# NB-IoT_1_0_0_final.net
KiCad netlist of a schematic drawn in Altium Designer
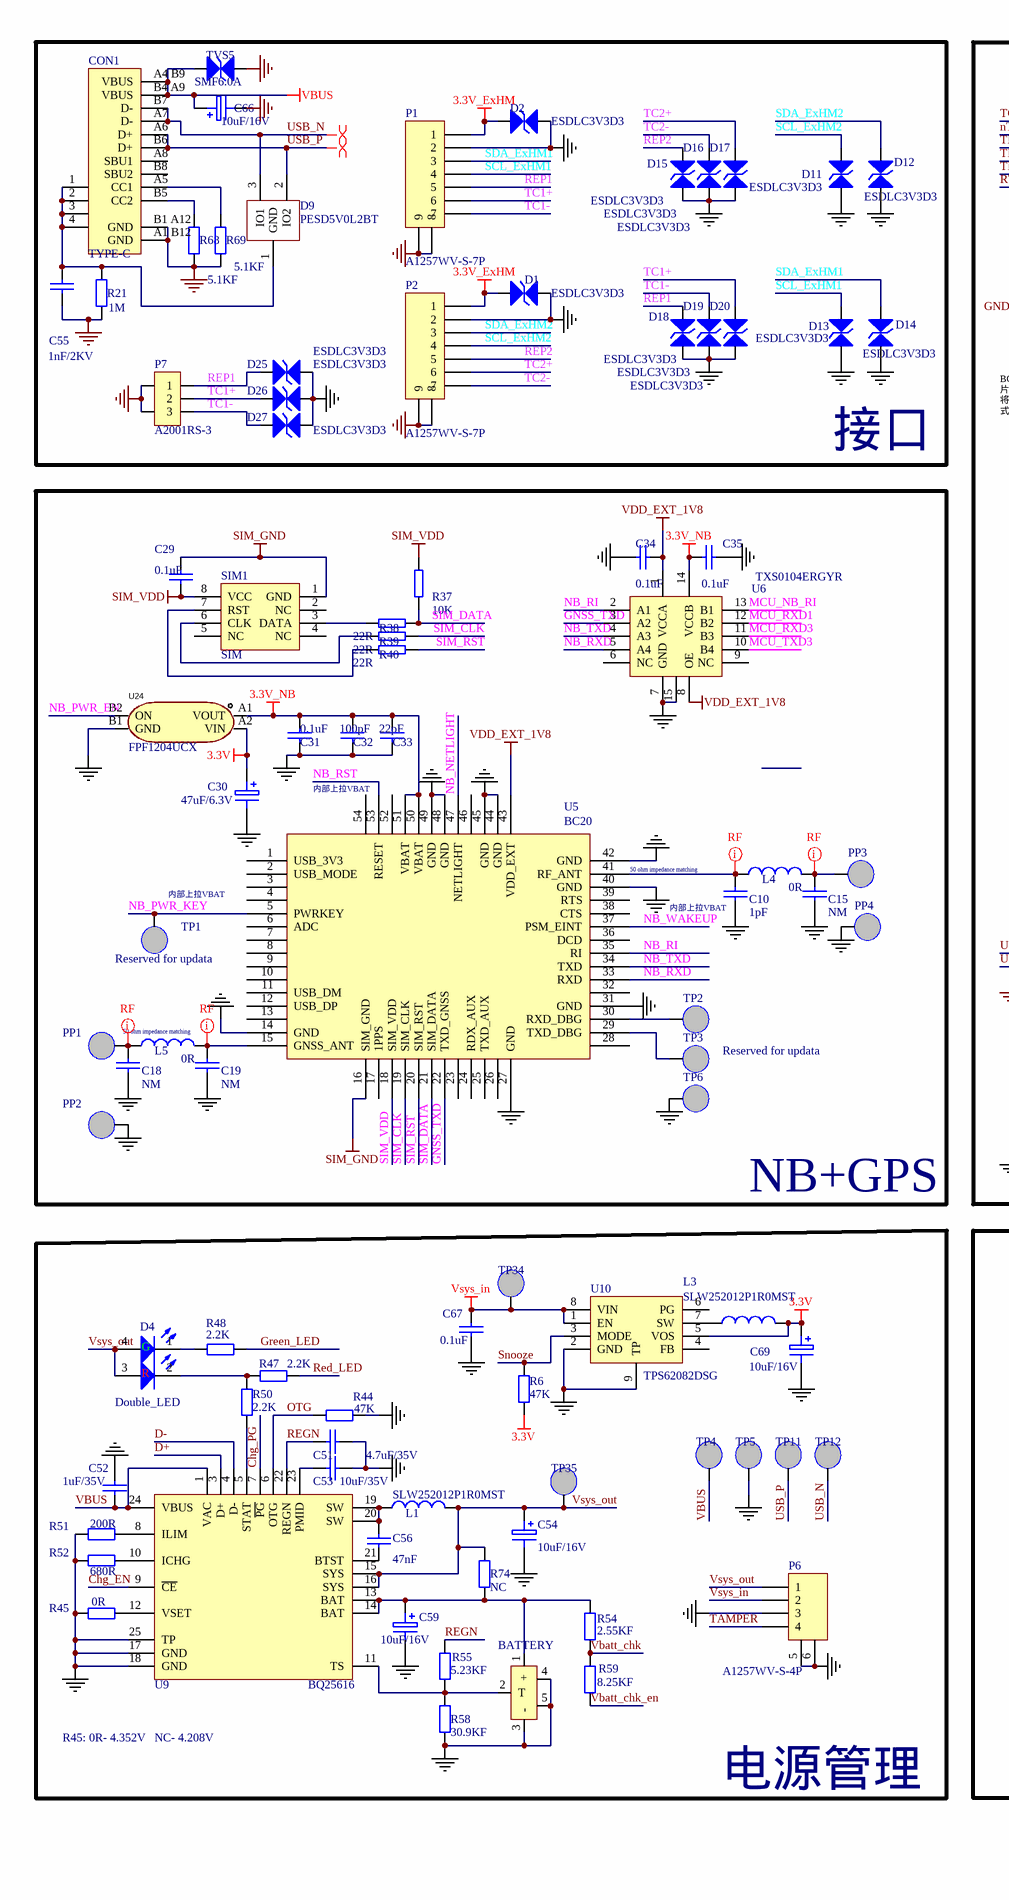
[diagram p0: NB-IoT_1.0.0_final.SchDoc, left]
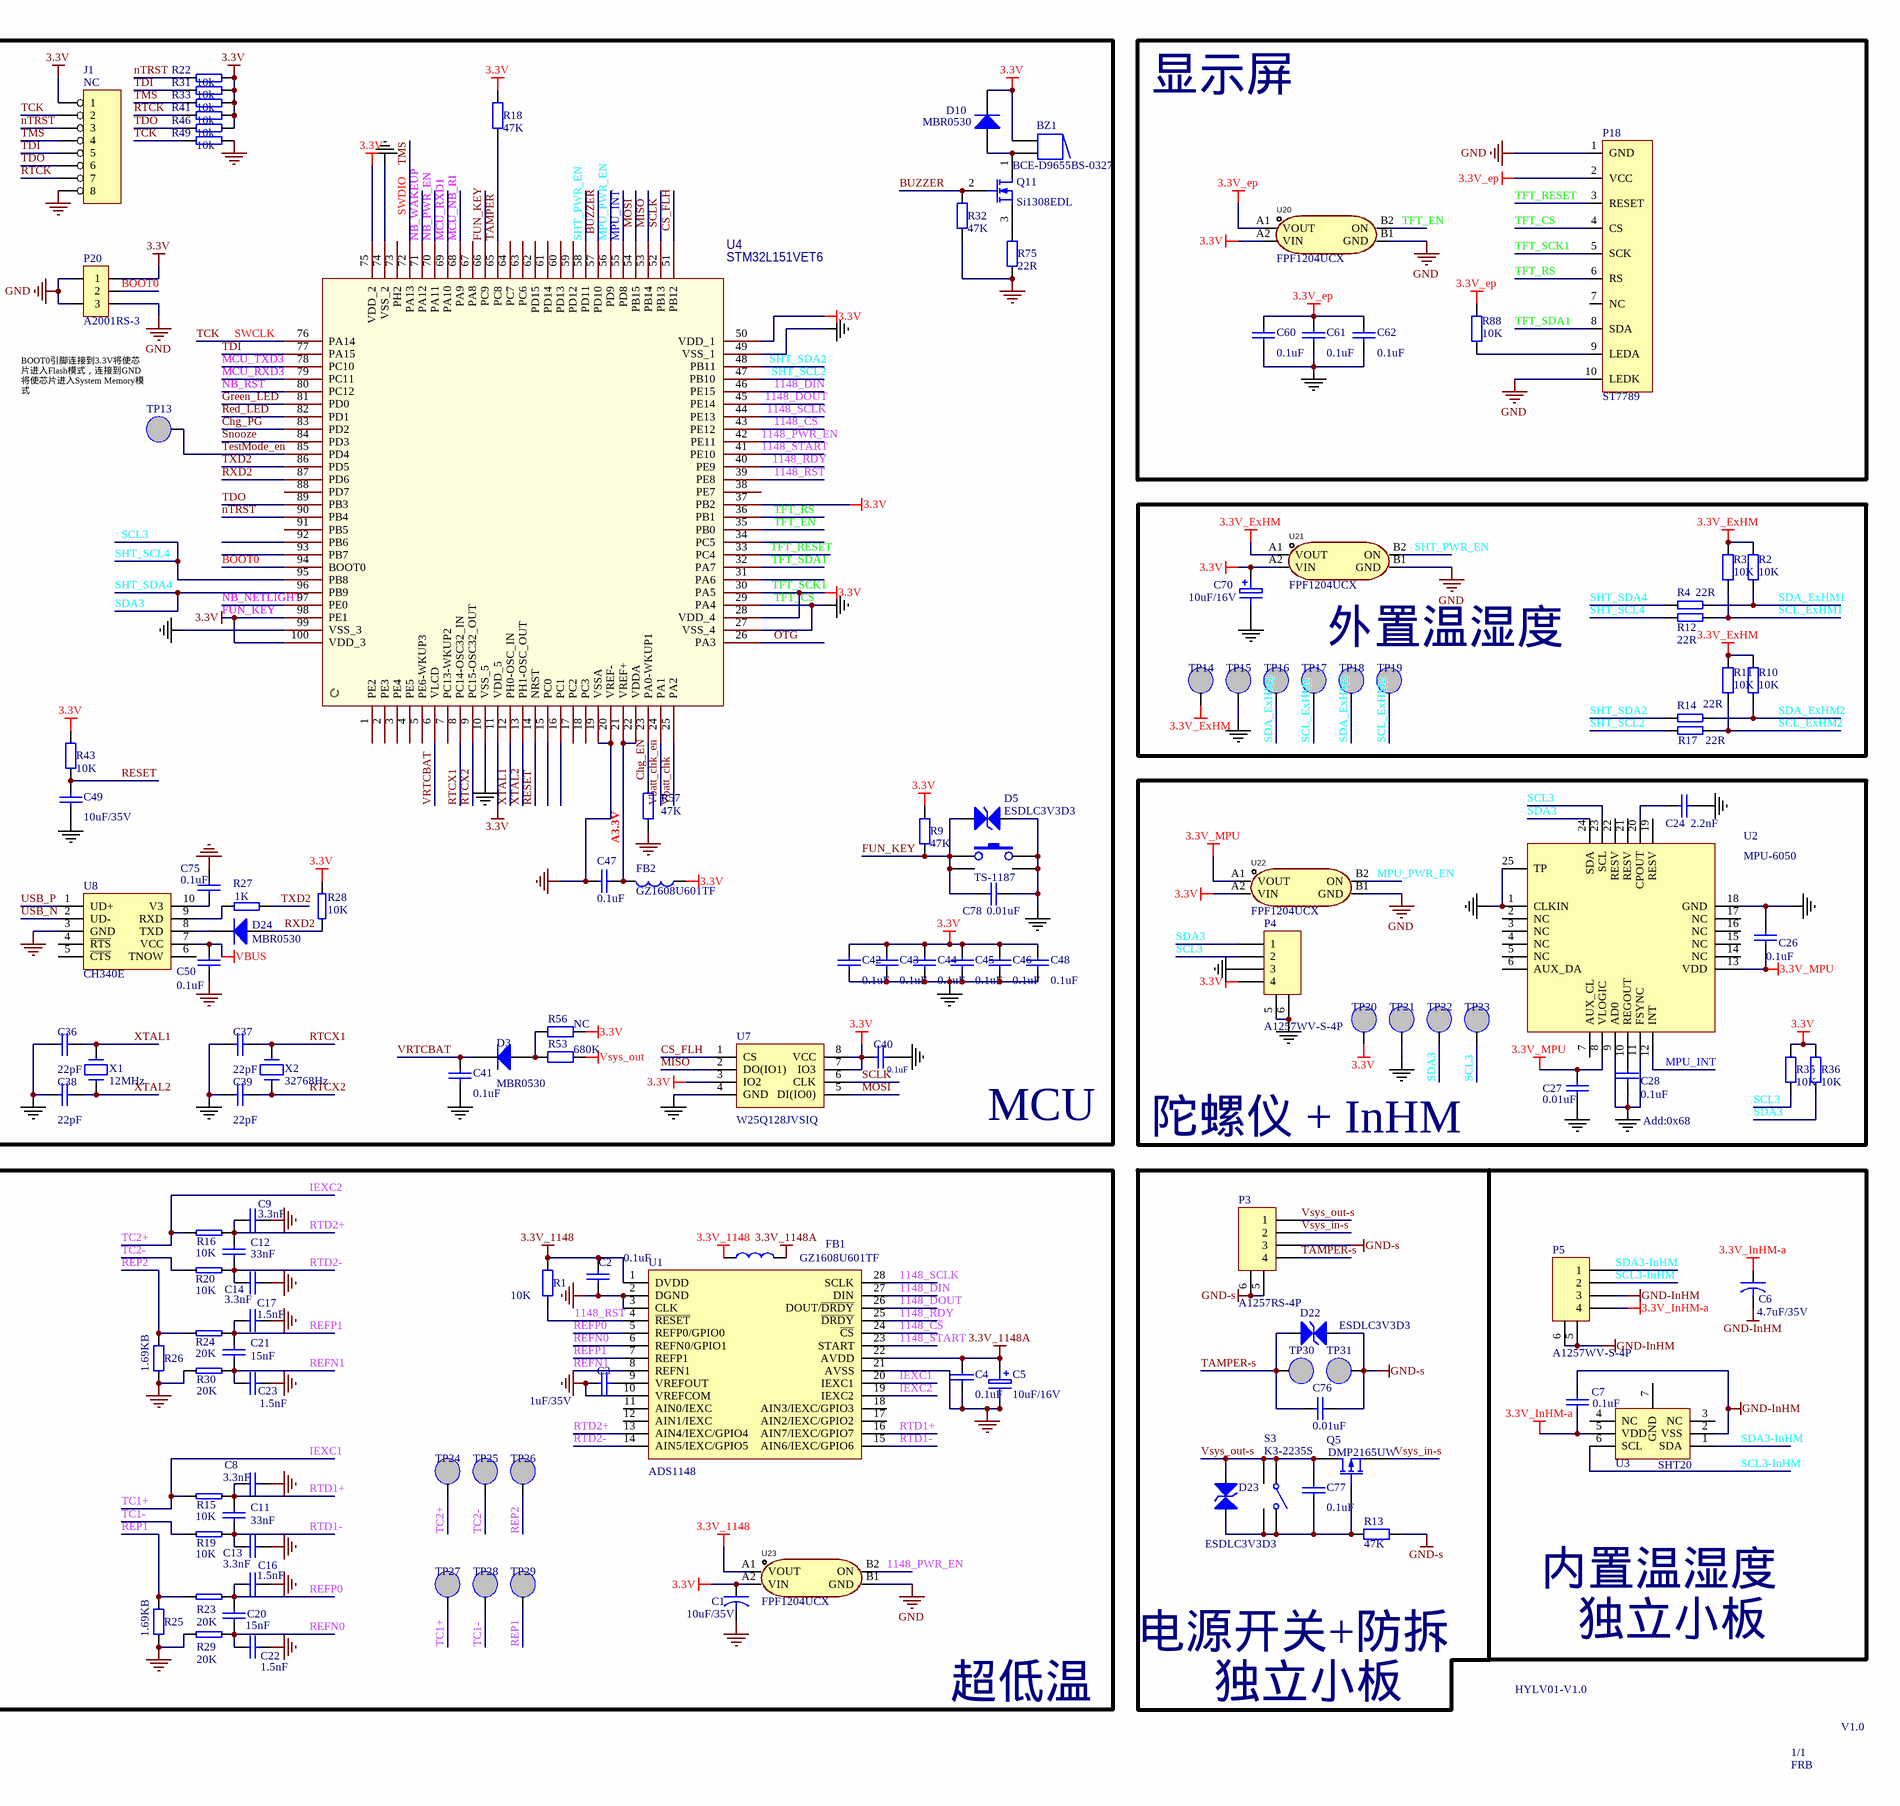
[diagram p1: NB-IoT_1.0.0_final.SchDoc, right]

(export (version "E")
  (design (tool "Eeschema 10.0.6"))
  (components
    (comp (ref "BT1") (value "BATTERY") (footprint "2.0T-3P") (libsource (lib "MFT_1") (part "BATT")))
    (comp (ref "BZ1")
      (value "BCE-D9655BS-0327")
      (footprint "BCE-D9655BS-0327")
      (description "Magnetic Transducer Buzzer")
      (fields (field (name "PUBLISHER") "Altium Limited"))
      (libsource (lib "Miscellaneous Devices") (part "Buzzer"))
    )
    (comp (ref "C1")
      (value "10uF/35V")
      (footprint "0805")
      (description "Capacitor")
      (libsource (lib "*") (part "CAPACITOR"))
    )
    (comp (ref "C2")
      (value "0.1uF")
      (footprint "C0402")
      (description "Capacitor")
      (libsource (lib "") (part "CAP_2"))
    )
    (comp (ref "C3")
      (value "1uF/35V")
      (footprint "C0402")
      (description "Capacitor")
      (libsource (lib "") (part "CAP_1"))
    )
    (comp (ref "C4")
      (value "0.1uF")
      (footprint "C0402")
      (description "Capacitor")
      (libsource (lib "") (part "CAP_2"))
    )
    (comp (ref "C5") (value "10uF/16V") (footprint "3216") (libsource (lib "MFT_1") (part "ELECTRO1")))
    (comp (ref "C6")
      (value "4.7uF/35V")
      (footprint "0603")
      (description "Capacitor")
      (libsource (lib "*") (part "CAPACITOR"))
    )
    (comp (ref "C7")
      (value "0.1uF")
      (footprint "C0402")
      (description "Capacitor")
      (libsource (lib "") (part "CAP_2"))
    )
    (comp (ref "C8")
      (value "3.3nF")
      (footprint "C0402")
      (description "Capacitor")
      (libsource (lib "") (part "CAP_1"))
    )
    (comp (ref "C9")
      (value "3.3nF")
      (footprint "C0402")
      (description "Capacitor")
      (libsource (lib "") (part "CAP_1"))
    )
    (comp (ref "C10") (value "1pF") (footprint "C0402") (libsource (lib "*") (part "CAP")))
    (comp (ref "C11")
      (value "33nF")
      (footprint "C0402")
      (description "Capacitor")
      (libsource (lib "") (part "CAP_1"))
    )
    (comp (ref "C12")
      (value "33nF")
      (footprint "C0402")
      (description "Capacitor")
      (libsource (lib "") (part "CAP_1"))
    )
    (comp (ref "C13")
      (value "3.3nF")
      (footprint "C0402")
      (description "Capacitor")
      (libsource (lib "") (part "CAP_1"))
    )
    (comp (ref "C14")
      (value "3.3nF")
      (footprint "C0402")
      (description "Capacitor")
      (libsource (lib "") (part "CAP_1"))
    )
    (comp (ref "C15") (value "NM") (footprint "C0402") (libsource (lib "*") (part "CAP")))
    (comp (ref "C16")
      (value "1.5nF")
      (footprint "C0402")
      (description "Capacitor")
      (libsource (lib "") (part "CAP_1"))
    )
    (comp (ref "C17")
      (value "1.5nF")
      (footprint "C0402")
      (description "Capacitor")
      (libsource (lib "") (part "CAP_1"))
    )
    (comp (ref "C18") (value "NM") (footprint "C0402") (libsource (lib "*") (part "CAP")))
    (comp (ref "C19") (value "NM") (footprint "C0402") (libsource (lib "*") (part "CAP")))
    (comp (ref "C20")
      (value "15nF")
      (footprint "C0402")
      (description "Capacitor")
      (libsource (lib "") (part "CAP_1"))
    )
    (comp (ref "C21")
      (value "15nF")
      (footprint "C0402")
      (description "Capacitor")
      (libsource (lib "") (part "CAP_1"))
    )
    (comp (ref "C22")
      (value "1.5nF")
      (footprint "C0402")
      (description "Capacitor")
      (libsource (lib "") (part "CAP_1"))
    )
    (comp (ref "C23")
      (value "1.5nF")
      (footprint "C0402")
      (description "Capacitor")
      (libsource (lib "") (part "CAP_1"))
    )
    (comp (ref "C24") (value "2.2nF") (footprint "C0402") (libsource (lib "DAQ") (part "CAP")))
    (comp (ref "C26") (value "0.1uF") (footprint "C0402") (libsource (lib "DAQ") (part "CAP")))
    (comp (ref "C27") (value "0.01uF") (footprint "C0402") (libsource (lib "DAQ") (part "CAP")))
    (comp (ref "C28") (value "0.1uF") (footprint "C0402") (libsource (lib "DAQ") (part "CAP")))
    (comp (ref "C29")
      (value "0.1uF")
      (footprint "C0402")
      (description "Capacitor")
      (libsource (lib "") (part "CAP_1"))
    )
    (comp (ref "C30") (value "47uF/6.3V") (footprint "3216") (libsource (lib "MFT_1") (part "ELECTRO1")))
    (comp (ref "C31") (value "0.1uF") (footprint "C0402") (libsource (lib "DAQ") (part "CAP")))
    (comp (ref "C32") (value "100pF") (footprint "C0402") (libsource (lib "DAQ") (part "CAP")))
    (comp (ref "C33") (value "22pF") (footprint "C0402") (libsource (lib "DAQ") (part "CAP")))
    (comp (ref "C34") (value "0.1uF") (footprint "C0402") (libsource (lib "DAQ") (part "CAP")))
    (comp (ref "C35") (value "0.1uF") (footprint "C0402") (libsource (lib "DAQ") (part "CAP")))
    (comp (ref "C36") (value "22pF") (footprint "C0402") (libsource (lib "*") (part "CAP")))
    (comp (ref "C37") (value "22pF") (footprint "C0402") (libsource (lib "*") (part "CAP")))
    (comp (ref "C38") (value "22pF") (footprint "C0402") (libsource (lib "*") (part "CAP")))
    (comp (ref "C39") (value "22pF") (footprint "C0402") (libsource (lib "*") (part "CAP")))
    (comp (ref "C40")
      (value "0.1uF")
      (footprint "C0402")
      (description "Capacitor")
      (libsource (lib "") (part "CAP_1"))
    )
    (comp (ref "C41")
      (value "0.1uF")
      (footprint "C0402")
      (description "Capacitor")
      (libsource (lib "") (part "CAP_2"))
    )
    (comp (ref "C42")
      (value "0.1uF")
      (footprint "C0402")
      (description "Capacitor")
      (libsource (lib "") (part "CAP_1"))
    )
    (comp (ref "C43")
      (value "0.1uF")
      (footprint "C0402")
      (description "Capacitor")
      (libsource (lib "") (part "CAP_1"))
    )
    (comp (ref "C44")
      (value "0.1uF")
      (footprint "C0402")
      (description "Capacitor")
      (libsource (lib "") (part "CAP_1"))
    )
    (comp (ref "C45")
      (value "0.1uF")
      (footprint "C0402")
      (description "Capacitor")
      (libsource (lib "") (part "CAP_1"))
    )
    (comp (ref "C46")
      (value "0.1uF")
      (footprint "C0402")
      (description "Capacitor")
      (libsource (lib "") (part "CAP_1"))
    )
    (comp (ref "C47")
      (value "0.1uF")
      (footprint "C0402")
      (description "Capacitor")
      (libsource (lib "") (part "CAP_1"))
    )
    (comp (ref "C48")
      (value "0.1uF")
      (footprint "C0402")
      (description "Capacitor")
      (libsource (lib "") (part "CAP_1"))
    )
    (comp (ref "C49")
      (value "10uF/35V")
      (footprint "0805")
      (description "Capacitor")
      (libsource (lib "") (part "CAP_1"))
    )
    (comp (ref "C50")
      (value "0.1uF")
      (footprint "C0402")
      (description "Capacitor")
      (libsource (lib "") (part "CAP_1"))
    )
    (comp (ref "C51") (value "4.7uF/35V") (footprint "0603") (libsource (lib "DAQ") (part "CAP")))
    (comp (ref "C52") (value "1uF/35V") (footprint "C0402") (libsource (lib "DAQ") (part "CAP")))
    (comp (ref "C53") (value "10uF/35V") (footprint "0805") (libsource (lib "DAQ") (part "CAP")))
    (comp (ref "C54") (value "10uF/16V") (footprint "3216") (libsource (lib "MFT_1") (part "ELECTRO1")))
    (comp (ref "C55") (value "1nF/2KV") (footprint "1206") (libsource (lib "DAQ") (part "CAP")))
    (comp (ref "C56") (value "47nF") (footprint "C0402") (libsource (lib "DAQ") (part "CAP")))
    (comp (ref "C59") (value "10uF/16V") (footprint "3216") (libsource (lib "MFT_1") (part "ELECTRO1")))
    (comp (ref "C60")
      (value "0.1uF")
      (footprint "C0402")
      (description "Capacitor")
      (libsource (lib "") (part "CAP_1"))
    )
    (comp (ref "C61")
      (value "0.1uF")
      (footprint "C0402")
      (description "Capacitor")
      (libsource (lib "") (part "CAP_1"))
    )
    (comp (ref "C62")
      (value "0.1uF")
      (footprint "C0402")
      (description "Capacitor")
      (libsource (lib "") (part "CAP_1"))
    )
    (comp (ref "C66") (value "10uF/16V") (footprint "3216") (libsource (lib "*") (part "ELECTRO1")))
    (comp (ref "C67") (value "0.1uF") (footprint "C0402") (libsource (lib "*") (part "CAP")))
    (comp (ref "C69") (value "10uF/16V") (footprint "3216") (libsource (lib "MFT_1") (part "ELECTRO1")))
    (comp (ref "C70") (value "10uF/16V") (footprint "3216") (libsource (lib "MFT_1") (part "ELECTRO1")))
    (comp (ref "C75")
      (value "0.1uF")
      (footprint "C0402")
      (description "Capacitor")
      (libsource (lib "") (part "CAP_1"))
    )
    (comp (ref "C76")
      (value "0.01uF")
      (footprint "C0402")
      (description "Capacitor")
      (libsource (lib "") (part "CAP_2"))
    )
    (comp (ref "C77")
      (value "0.1uF")
      (footprint "C0402")
      (description "Capacitor")
      (libsource (lib "") (part "CAP_2"))
    )
    (comp (ref "C78")
      (value "0.01uF")
      (footprint "C0402")
      (description "Capacitor")
      (libsource (lib "") (part "CAP_2"))
    )
    (comp (ref "CON1") (value "TYPE-C") (footprint "TypeC_L-1") (libsource (lib "MFT_1") (part "TYPE-C")))
    (comp (ref "D1") (value "ESDLC3V3D3") (footprint "SOD-323") (libsource (lib "*") (part "TVS")))
    (comp (ref "D2") (value "ESDLC3V3D3") (footprint "SOD-323") (libsource (lib "*") (part "TVS")))
    (comp (ref "D3")
      (value "MBR0530")
      (footprint "SOD-123")
      (description "Default Diode")
      (fields (field (name "PUBLISHER") "Altium Limited"))
      (libsource (lib "Miscellaneous Devices") (part "Diode"))
    )
    (comp (ref "D4")
      (value "Double_LED")
      (footprint "LED0805D")
      (libsource (lib "MFT_1") (part "LED_DOUBLE"))
    )
    (comp (ref "D5") (value "ESDLC3V3D3") (footprint "SOD-323") (libsource (lib "*") (part "TVS")))
    (comp (ref "D9")
      (value "PESD5V0L2BT")
      (footprint "SOT-23")
      (description "PESD15VL2BT")
      (libsource (lib "*") (part "ESD2B"))
    )
    (comp (ref "D10")
      (value "MBR0530")
      (footprint "SOD-123")
      (description "Default Diode")
      (fields (field (name "PUBLISHER") "Altium Limited"))
      (libsource (lib "Miscellaneous Devices") (part "Diode"))
    )
    (comp (ref "D11") (value "ESDLC3V3D3") (footprint "SOD-323") (libsource (lib "*") (part "TVS")))
    (comp (ref "D12") (value "ESDLC3V3D3") (footprint "SOD-323") (libsource (lib "*") (part "TVS")))
    (comp (ref "D13") (value "ESDLC3V3D3") (footprint "SOD-323") (libsource (lib "*") (part "TVS")))
    (comp (ref "D14") (value "ESDLC3V3D3") (footprint "SOD-323") (libsource (lib "*") (part "TVS")))
    (comp (ref "D15") (value "ESDLC3V3D3") (footprint "SOD-323") (libsource (lib "*") (part "TVS")))
    (comp (ref "D16") (value "ESDLC3V3D3") (footprint "SOD-323") (libsource (lib "*") (part "TVS")))
    (comp (ref "D17") (value "ESDLC3V3D3") (footprint "SOD-323") (libsource (lib "*") (part "TVS")))
    (comp (ref "D18") (value "ESDLC3V3D3") (footprint "SOD-323") (libsource (lib "*") (part "TVS")))
    (comp (ref "D19") (value "ESDLC3V3D3") (footprint "SOD-323") (libsource (lib "*") (part "TVS")))
    (comp (ref "D20") (value "ESDLC3V3D3") (footprint "SOD-323") (libsource (lib "*") (part "TVS")))
    (comp (ref "D22") (value "ESDLC3V3D3") (footprint "SOD-323") (libsource (lib "*") (part "TVS")))
    (comp (ref "D23") (value "ESDLC3V3D3") (footprint "SOD-323") (libsource (lib "*") (part "TVS")))
    (comp (ref "D24")
      (value "MBR0530")
      (footprint "SOD-123")
      (description "Default Diode")
      (fields (field (name "PUBLISHER") "Altium Limited"))
      (libsource (lib "Miscellaneous Devices") (part "Diode"))
    )
    (comp (ref "D25") (value "ESDLC3V3D3") (footprint "SOD-323") (libsource (lib "*") (part "TVS")))
    (comp (ref "D26") (value "ESDLC3V3D3") (footprint "SOD-323") (libsource (lib "*") (part "TVS")))
    (comp (ref "D27") (value "ESDLC3V3D3") (footprint "SOD-323") (libsource (lib "*") (part "TVS")))
    (comp (ref "FB1") (value "GZ1608U601TF") (footprint "0603") (libsource (lib "*") (part "INDUCTOR1")))
    (comp (ref "FB2") (value "GZ1608U601TF") (footprint "0603") (libsource (lib "") (part "INDUCTOR1_1")))
    (comp (ref "J1")
      (value "NC")
      (footprint "1.25*8")
      (description "8 Pin Header")
      (libsource (lib "*") (part "8 HEADER"))
    )
    (comp (ref "L1")
      (value "SLW252012P1R0MST")
      (footprint "2520")
      (description "Inductor")
      (fields (field (name "PUBLISHER") "Altium Limited"))
      (libsource (lib "Miscellaneous Devices") (part "Inductor"))
    )
    (comp (ref "L3")
      (value "SLW252012P1R0MST")
      (footprint "2520")
      (description "Inductor")
      (fields (field (name "PUBLISHER") "Altium Limited"))
      (libsource (lib "Miscellaneous Devices") (part "Inductor"))
    )
    (comp (ref "L4")
      (value "0R")
      (footprint "0402")
      (description "Inductor")
      (fields (field (name "PUBLISHER") "Altium Limited"))
      (libsource (lib "Miscellaneous Devices") (part "Inductor"))
    )
    (comp (ref "L5")
      (value "0R")
      (footprint "0402")
      (description "Inductor")
      (fields (field (name "PUBLISHER") "Altium Limited"))
      (libsource (lib "Miscellaneous Devices") (part "Inductor"))
    )
    (comp (ref "P1")
      (value "A1257WV-S-7P")
      (footprint "A1257WV-S-7P")
      (description "Header, 7-Pin")
      (fields (field (name "PUBLISHER") "Altium Limited"))
      (libsource (lib "MFT") (part "Header 7"))
    )
    (comp (ref "P2")
      (value "A1257WV-S-7P")
      (footprint "A1257WV-S-7P")
      (description "Header, 7-Pin")
      (fields (field (name "PUBLISHER") "Altium Limited"))
      (libsource (lib "MFT") (part "Header 7"))
    )
    (comp (ref "P3")
      (value "A1257RS-4P")
      (footprint "A1257WV-S-4P")
      (description "Header, 4-Pin")
      (fields (field (name "PUBLISHER") "Altium Limited"))
      (libsource (lib "") (part "Header 4_1"))
    )
    (comp (ref "P4")
      (value "A1257WV-S-4P")
      (footprint "A1257WV-S-4P")
      (description "Header, 4-Pin")
      (fields (field (name "PUBLISHER") "Altium Limited"))
      (libsource (lib "MFT") (part "Header 4"))
    )
    (comp (ref "P5")
      (value "A1257WV-S-4P")
      (footprint "A1257WV-S-4P")
      (description "Header, 4-Pin")
      (fields (field (name "PUBLISHER") "Altium Limited"))
      (libsource (lib "") (part "Header 4_1"))
    )
    (comp (ref "P6")
      (value "A1257WV-S-4P")
      (footprint "A1257WV-S-4P")
      (description "Header, 4-Pin")
      (fields (field (name "PUBLISHER") "Altium Limited"))
      (libsource (lib "MFT") (part "Header 4"))
    )
    (comp (ref "P7") (value "A2001RS-3") (footprint "2.0T-3P") (libsource (lib "MFT_1") (part "A2001RS-3")))
    (comp (ref "P18")
      (value "ST7789")
      (footprint "FPC-SMD_P0.5-10P_FGS-XJ-H2.0")
      (libsource (lib "nb-iot") (part "ST7789"))
    )
    (comp (ref "P20") (value "A2001RS-3") (footprint "2.0T-3P") (libsource (lib "MFT_1") (part "A2001RS-3")))
    (comp (ref "PP1") (value "~") (footprint "TP2.2") (libsource (lib "MFT_1") (part "tp")))
    (comp (ref "PP2") (value "~") (footprint "TP2.2") (libsource (lib "MFT_1") (part "tp")))
    (comp (ref "PP3") (value "~") (footprint "TP2.2") (libsource (lib "MFT_1") (part "tp")))
    (comp (ref "PP4") (value "~") (footprint "TP2.2") (libsource (lib "MFT_1") (part "tp")))
    (comp (ref "Q5")
      (value "DMP2165UW")
      (footprint "SOT-323")
      (description "P-Channel MOSFET")
      (fields (field (name "PUBLISHER") "Altium Limited"))
      (libsource (lib "Miscellaneous Devices") (part "MOSFET-P"))
    )
    (comp (ref "Q11")
      (value "Si1308EDL")
      (footprint "SOT-323")
      (description "N-Channel MOSFET")
      (fields (field (name "PUBLISHER") "Altium Limited"))
      (libsource (lib "MFT_1") (part "MOSFET-N"))
    )
    (comp (ref "R1")
      (value "10K")
      (footprint "0402")
      (description "Resistor")
      (fields (field (name "PUBLISHER") "Altium Limited"))
      (libsource (lib "") (part "Res2_3"))
    )
    (comp (ref "R2")
      (value "10K")
      (footprint "0402")
      (description "Resistor")
      (fields (field (name "PUBLISHER") "Altium Limited"))
      (libsource (lib "Miscellaneous Devices") (part "Res2"))
    )
    (comp (ref "R3")
      (value "10K")
      (footprint "0402")
      (description "Resistor")
      (fields (field (name "PUBLISHER") "Altium Limited"))
      (libsource (lib "Miscellaneous Devices") (part "Res2"))
    )
    (comp (ref "R4") (value "22R") (footprint "0402") (libsource (lib "*") (part "RES2")))
    (comp (ref "R6")
      (value "47K")
      (footprint "0402")
      (description "Resistor")
      (fields (field (name "PUBLISHER") "Altium Limited"))
      (libsource (lib "") (part "Res2_1"))
    )
    (comp (ref "R9")
      (value "47K")
      (footprint "0402")
      (description "Resistor")
      (fields (field (name "PUBLISHER") "Altium Limited"))
      (libsource (lib "") (part "Res2_1"))
    )
    (comp (ref "R10")
      (value "10K")
      (footprint "0402")
      (description "Resistor")
      (fields (field (name "PUBLISHER") "Altium Limited"))
      (libsource (lib "Miscellaneous Devices") (part "Res2"))
    )
    (comp (ref "R11")
      (value "10K")
      (footprint "0402")
      (description "Resistor")
      (fields (field (name "PUBLISHER") "Altium Limited"))
      (libsource (lib "Miscellaneous Devices") (part "Res2"))
    )
    (comp (ref "R12") (value "22R") (footprint "0402") (libsource (lib "*") (part "RES2")))
    (comp (ref "R13")
      (value "47K")
      (footprint "0402")
      (description "Resistor")
      (fields (field (name "PUBLISHER") "Altium Limited"))
      (libsource (lib "") (part "Res2_2"))
    )
    (comp (ref "R14") (value "22R") (footprint "0402") (libsource (lib "*") (part "RES2")))
    (comp (ref "R15") (value "10K") (footprint "0402") (libsource (lib "*") (part "RES")))
    (comp (ref "R16") (value "10K") (footprint "0402") (libsource (lib "*") (part "RES")))
    (comp (ref "R17") (value "22R") (footprint "0402") (libsource (lib "*") (part "RES2")))
    (comp (ref "R18")
      (value "47K")
      (footprint "0402")
      (description "Resistor")
      (fields (field (name "PUBLISHER") "Altium Limited"))
      (libsource (lib "") (part "Res2_1"))
    )
    (comp (ref "R19") (value "10K") (footprint "0402") (libsource (lib "*") (part "RES")))
    (comp (ref "R20") (value "10K") (footprint "0402") (libsource (lib "*") (part "RES")))
    (comp (ref "R21")
      (value "1M")
      (footprint "0603")
      (description "Resistor")
      (fields (field (name "PUBLISHER") "Altium Limited"))
      (libsource (lib "") (part "Res2_1"))
    )
    (comp (ref "R22") (value "10k") (footprint "0402") (libsource (lib "*") (part "RES2")))
    (comp (ref "R23") (value "20K") (footprint "0402") (libsource (lib "*") (part "RES")))
    (comp (ref "R24") (value "20K") (footprint "0402") (libsource (lib "*") (part "RES")))
    (comp (ref "R25")
      (value "1.69KB")
      (footprint "0402")
      (description "Resistor")
      (fields (field (name "PUBLISHER") "Altium Limited"))
      (libsource (lib "") (part "Res2_1"))
    )
    (comp (ref "R26")
      (value "1.69KB")
      (footprint "0402")
      (description "Resistor")
      (fields (field (name "PUBLISHER") "Altium Limited"))
      (libsource (lib "") (part "Res2_1"))
    )
    (comp (ref "R27") (value "1K") (footprint "0402") (libsource (lib "*") (part "RES2")))
    (comp (ref "R28") (value "10K") (footprint "0402") (libsource (lib "*") (part "RES2")))
    (comp (ref "R29") (value "20K") (footprint "0402") (libsource (lib "*") (part "RES")))
    (comp (ref "R30") (value "20K") (footprint "0402") (libsource (lib "*") (part "RES")))
    (comp (ref "R31") (value "10k") (footprint "0402") (libsource (lib "*") (part "RES2")))
    (comp (ref "R32")
      (value "47K")
      (footprint "0402")
      (description "Resistor")
      (fields (field (name "PUBLISHER") "Altium Limited"))
      (libsource (lib "") (part "Res2_1"))
    )
    (comp (ref "R33") (value "10k") (footprint "0402") (libsource (lib "*") (part "RES2")))
    (comp (ref "R35")
      (value "10K")
      (footprint "0402")
      (description "Resistor")
      (fields (field (name "PUBLISHER") "Altium Limited"))
      (libsource (lib "") (part "Res2_1"))
    )
    (comp (ref "R36")
      (value "10K")
      (footprint "0402")
      (description "Resistor")
      (fields (field (name "PUBLISHER") "Altium Limited"))
      (libsource (lib "") (part "Res2_1"))
    )
    (comp (ref "R37") (value "10K") (footprint "0402") (libsource (lib "*") (part "RES2")))
    (comp (ref "R38") (value "22R") (footprint "0402") (libsource (lib "*") (part "RES2")))
    (comp (ref "R39") (value "22R") (footprint "0402") (libsource (lib "*") (part "RES2")))
    (comp (ref "R40") (value "22R") (footprint "0402") (libsource (lib "*") (part "RES2")))
    (comp (ref "R41") (value "10k") (footprint "0402") (libsource (lib "*") (part "RES2")))
    (comp (ref "R43")
      (value "10K")
      (footprint "0402")
      (description "Resistor")
      (fields (field (name "PUBLISHER") "*"))
      (libsource (lib "*") (part "Res2"))
    )
    (comp (ref "R44")
      (value "47K")
      (footprint "0402")
      (description "Resistor")
      (fields (field (name "PUBLISHER") "Altium Limited"))
      (libsource (lib "") (part "Res2_2"))
    )
    (comp (ref "R45")
      (value "0R")
      (footprint "0402")
      (description "Resistor")
      (fields (field (name "PUBLISHER") "Altium Limited"))
      (libsource (lib "Miscellaneous Devices") (part "Res2"))
    )
    (comp (ref "R46") (value "10k") (footprint "0402") (libsource (lib "*") (part "RES2")))
    (comp (ref "R47")
      (value "2.2K")
      (footprint "0402")
      (description "Resistor")
      (fields (field (name "PUBLISHER") "Altium Limited"))
      (libsource (lib "") (part "Res2_2"))
    )
    (comp (ref "R48")
      (value "2.2K")
      (footprint "0402")
      (description "Resistor")
      (fields (field (name "PUBLISHER") "Altium Limited"))
      (libsource (lib "") (part "Res2_2"))
    )
    (comp (ref "R49") (value "10k") (footprint "0402") (libsource (lib "*") (part "RES2")))
    (comp (ref "R50")
      (value "2.2K")
      (footprint "0402")
      (description "Resistor")
      (fields (field (name "PUBLISHER") "Altium Limited"))
      (libsource (lib "") (part "Res2_3"))
    )
    (comp (ref "R51")
      (value "200R")
      (footprint "0402")
      (description "Resistor")
      (fields (field (name "PUBLISHER") "Altium Limited"))
      (libsource (lib "Miscellaneous Devices") (part "Res2"))
    )
    (comp (ref "R52")
      (value "680R")
      (footprint "0402")
      (description "Resistor")
      (fields (field (name "PUBLISHER") "Altium Limited"))
      (libsource (lib "Miscellaneous Devices") (part "Res2"))
    )
    (comp (ref "R53")
      (value "680K")
      (footprint "0402")
      (description "Resistor")
      (fields (field (name "PUBLISHER") "Altium Limited"))
      (libsource (lib "Miscellaneous Devices") (part "Res2"))
    )
    (comp (ref "R54")
      (value "2.55KF")
      (footprint "0402")
      (description "Resistor")
      (fields (field (name "PUBLISHER") "Altium Limited"))
      (libsource (lib "") (part "Res2_3"))
    )
    (comp (ref "R55")
      (value "5.23KF")
      (footprint "0402")
      (description "Resistor")
      (fields (field (name "PUBLISHER") "Altium Limited"))
      (libsource (lib "") (part "Res2_3"))
    )
    (comp (ref "R56")
      (value "NC")
      (footprint "0402")
      (description "Resistor")
      (fields (field (name "PUBLISHER") "Altium Limited"))
      (libsource (lib "") (part "Res2_2"))
    )
    (comp (ref "R57")
      (value "47K")
      (footprint "0402")
      (description "Resistor")
      (fields (field (name "PUBLISHER") "Altium Limited"))
      (libsource (lib "") (part "Res2_1"))
    )
    (comp (ref "R58")
      (value "30.9KF")
      (footprint "0402")
      (description "Resistor")
      (fields (field (name "PUBLISHER") "Altium Limited"))
      (libsource (lib "") (part "Res2_1"))
    )
    (comp (ref "R59")
      (value "8.25KF")
      (footprint "0402")
      (description "Resistor")
      (fields (field (name "PUBLISHER") "Altium Limited"))
      (libsource (lib "") (part "Res2_3"))
    )
    (comp (ref "R68")
      (value "5.1KF")
      (footprint "0402")
      (description "Resistor")
      (fields (field (name "PUBLISHER") "Altium Limited"))
      (libsource (lib "") (part "Res2_1"))
    )
    (comp (ref "R69")
      (value "5.1KF")
      (footprint "0402")
      (description "Resistor")
      (fields (field (name "PUBLISHER") "Altium Limited"))
      (libsource (lib "") (part "Res2_1"))
    )
    (comp (ref "R74")
      (value "NC")
      (footprint "0805")
      (description "Resistor")
      (fields (field (name "PUBLISHER") "Altium Limited"))
      (libsource (lib "") (part "Res2_3"))
    )
    (comp (ref "R75")
      (value "22R")
      (footprint "0402")
      (description "Resistor")
      (fields (field (name "PUBLISHER") "Altium Limited"))
      (libsource (lib "") (part "Res2_1"))
    )
    (comp (ref "R88")
      (value "10K")
      (footprint "0402")
      (description "Resistor")
      (fields (field (name "PUBLISHER") "Altium Limited"))
      (libsource (lib "Miscellaneous Devices") (part "Res2"))
    )
    (comp (ref "S2") (value "TS-1187") (footprint "TS-1187") (libsource (lib "MFT_1") (part "SW-PB")))
    (comp (ref "S3") (value "K3-2235S") (footprint "K3-2235S") (libsource (lib "MFT_1") (part "PWR_SW")))
    (comp (ref "SIM1") (value "SIM") (footprint "VQFN8") (libsource (lib "MFT_1") (part "SIM_chip")))
    (comp (ref "TP1") (value "~") (footprint "TP1.5") (libsource (lib "MFT_1") (part "tp")))
    (comp (ref "TP2") (value "~") (footprint "TP1.5") (libsource (lib "MFT_1") (part "tp")))
    (comp (ref "TP3") (value "~") (footprint "TP1.5") (libsource (lib "MFT_1") (part "tp")))
    (comp (ref "TP4") (value "~") (footprint "TP1.5") (libsource (lib "MFT_1") (part "tp")))
    (comp (ref "TP5") (value "~") (footprint "TP1.5") (libsource (lib "MFT_1") (part "tp")))
    (comp (ref "TP6") (value "~") (footprint "TP1.5") (libsource (lib "MFT_1") (part "tp")))
    (comp (ref "TP11") (value "~") (footprint "TP1.5") (libsource (lib "MFT_1") (part "tp")))
    (comp (ref "TP12") (value "~") (footprint "TP1.5") (libsource (lib "MFT_1") (part "tp")))
    (comp (ref "TP13") (value "~") (footprint "TP1.5") (libsource (lib "MFT_1") (part "tp")))
    (comp (ref "TP14") (value "~") (footprint "TP1.5") (libsource (lib "MFT_1") (part "tp")))
    (comp (ref "TP15") (value "~") (footprint "TP1.5") (libsource (lib "MFT_1") (part "tp")))
    (comp (ref "TP16") (value "~") (footprint "TP1.5") (libsource (lib "MFT_1") (part "tp")))
    (comp (ref "TP17") (value "~") (footprint "TP1.5") (libsource (lib "MFT_1") (part "tp")))
    (comp (ref "TP18") (value "~") (footprint "TP1.5") (libsource (lib "MFT_1") (part "tp")))
    (comp (ref "TP19") (value "~") (footprint "TP1.5") (libsource (lib "MFT_1") (part "tp")))
    (comp (ref "TP20") (value "~") (footprint "TP1.5") (libsource (lib "MFT_1") (part "tp")))
    (comp (ref "TP21") (value "~") (footprint "TP1.5") (libsource (lib "MFT_1") (part "tp")))
    (comp (ref "TP22") (value "~") (footprint "TP1.5") (libsource (lib "MFT_1") (part "tp")))
    (comp (ref "TP23") (value "~") (footprint "TP1.5") (libsource (lib "MFT_1") (part "tp")))
    (comp (ref "TP24") (value "~") (footprint "TP1.5") (libsource (lib "MFT_1") (part "tp")))
    (comp (ref "TP25") (value "~") (footprint "TP1.5") (libsource (lib "MFT_1") (part "tp")))
    (comp (ref "TP26") (value "~") (footprint "TP1.5") (libsource (lib "MFT_1") (part "tp")))
    (comp (ref "TP27") (value "~") (footprint "TP1.5") (libsource (lib "MFT_1") (part "tp")))
    (comp (ref "TP28") (value "~") (footprint "TP1.5") (libsource (lib "MFT_1") (part "tp")))
    (comp (ref "TP29") (value "~") (footprint "TP1.5") (libsource (lib "MFT_1") (part "tp")))
    (comp (ref "TP30") (value "~") (footprint "TP2.5") (libsource (lib "MFT_1") (part "tp")))
    (comp (ref "TP31") (value "~") (footprint "TP2.5") (libsource (lib "MFT_1") (part "tp")))
    (comp (ref "TP34") (value "~") (footprint "TP1.5") (libsource (lib "MFT_1") (part "tp")))
    (comp (ref "TP35") (value "~") (footprint "TP1.5") (libsource (lib "MFT_1") (part "tp")))
    (comp (ref "TVS5") (value "SMF6.0A") (footprint "SOD-123") (libsource (lib "*") (part "TVS")))
    (comp (ref "U1") (value "ADS1148") (footprint "TSSOP28") (libsource (lib "*") (part "ADS1148")))
    (comp (ref "U2") (value "MPU-6050") (footprint "QFN-24") (libsource (lib "MFT_1") (part "MPU-6050")))
    (comp (ref "U3") (value "SHT20") (footprint "DFN3X3") (libsource (lib "MFT") (part "SHT2X")))
    (comp (ref "U4")
      (value "STM32L151VET6")
      (footprint "LQFP-100_L14.0-W14.0-P0.50-LS16.0-BL")
      (fields (field (name "MANUFACTURER PART") "STM32L451VET6"))
      (libsource (lib "nb-iot") (part "STM32L451VET6"))
    )
    (comp (ref "U5") (value "BC20") (footprint "BC20") (libsource (lib "MFT") (part "BC20")))
    (comp (ref "U6") (value "TXS0104ERGYR") (footprint "VQFN-14") (libsource (lib "MFT_1") (part "TXS0104")))
    (comp (ref "U7") (value "W25Q128JVSIQ") (footprint "SOL-8") (libsource (lib "MFT_1") (part "25QXXX")))
    (comp (ref "U8") (value "CH340E") (footprint "MSOP-10") (libsource (lib "MFT_1") (part "CH340E")))
    (comp (ref "U9") (value "BQ25616") (footprint "VQFN-24") (libsource (lib "MFT_1") (part "BQ25606")))
    (comp (ref "U10")
      (value "TPS62082DSG")
      (footprint "WSON-8")
      (libsource (lib "MFT_1") (part "TPS62082DSG"))
    )
    (comp (ref "U20")
      (value "FPF1204UCX")
      (footprint "WLCSP-4_L0.85-W0.85-R2-C2-P0.40-BL")
      (description "功率电子开关")
      (libsource (lib "nb-iot") (part "FPF1204UCX"))
    )
    (comp (ref "U21")
      (value "FPF1204UCX")
      (footprint "WLCSP-4_L0.85-W0.85-R2-C2-P0.40-BL")
      (description "功率电子开关")
      (libsource (lib "nb-iot") (part "FPF1204UCX"))
    )
    (comp (ref "U22")
      (value "FPF1204UCX")
      (footprint "WLCSP-4_L0.85-W0.85-R2-C2-P0.40-BL")
      (description "功率电子开关")
      (libsource (lib "nb-iot") (part "FPF1204UCX"))
    )
    (comp (ref "U23")
      (value "FPF1204UCX")
      (footprint "WLCSP-4_L0.85-W0.85-R2-C2-P0.40-BL")
      (description "功率电子开关")
      (libsource (lib "nb-iot") (part "FPF1204UCX"))
    )
    (comp (ref "U24")
      (value "FPF1204UCX")
      (footprint "WLCSP-4_L0.85-W0.85-R2-C2-P0.40-BL")
      (description "功率电子开关")
      (libsource (lib "nb-iot") (part "FPF1204UCX"))
    )
    (comp (ref "X1") (value "12MHz") (footprint "3225") (libsource (lib "*") (part "CRYSTAL")))
    (comp (ref "X2") (value "32768Hz") (footprint "3215") (libsource (lib "*") (part "CRYSTAL")))
  )
  (nets
    (net (code "1") (name "/1148_DIN") (class "Default")
      (node (ref "U1") (pin "27") (pinfunction "DIN_27") (pintype "passive"))
      (node (ref "U4") (pin "46") (pinfunction "PE15_46") (pintype "passive"))
    )
    (net (code "2") (name "/1148_DOUT") (class "Default")
      (node (ref "U1") (pin "26") (pinfunction "DOUT/~{DRDY}_26") (pintype "passive"))
      (node (ref "U4") (pin "45") (pinfunction "PE14_45") (pintype "passive"))
    )
    (net (code "3") (name "/1148_PWR_EN") (class "Default")
      (node (ref "U23") (pin "B2") (pinfunction "ON_B2") (pintype "passive"))
      (node (ref "U4") (pin "42") (pinfunction "PE11_42") (pintype "passive"))
    )
    (net (code "4") (name "/1148_RDY") (class "Default")
      (node (ref "U1") (pin "25") (pinfunction "~{DRDY}_25") (pintype "passive"))
      (node (ref "U4") (pin "40") (pinfunction "PE9_40") (pintype "passive"))
    )
    (net (code "5") (name "/1148_RST") (class "Default")
      (node (ref "R1") (pin "2") (pinfunction "2_2") (pintype "passive"))
      (node (ref "U1") (pin "4") (pinfunction "~{RESET}_4") (pintype "passive"))
      (node (ref "U4") (pin "39") (pinfunction "PE8_39") (pintype "passive"))
    )
    (net (code "6") (name "/1148_SCLK") (class "Default")
      (node (ref "U1") (pin "28") (pinfunction "SCLK_28") (pintype "passive"))
      (node (ref "U4") (pin "44") (pinfunction "PE13_44") (pintype "passive"))
    )
    (net (code "7") (name "/1148_START") (class "Default")
      (node (ref "U1") (pin "23") (pinfunction "START_23") (pintype "passive"))
      (node (ref "U4") (pin "41") (pinfunction "PE10_41") (pintype "passive"))
    )
    (net (code "8") (name "/1148_~{CS}") (class "Default")
      (node (ref "U1") (pin "24") (pinfunction "~{CS}_24") (pintype "passive"))
      (node (ref "U4") (pin "43") (pinfunction "PE12_43") (pintype "passive"))
    )
    (net (code "9") (name "/A3.3V") (class "Default")
      (node (ref "C47") (pin "1") (pinfunction "1_1") (pintype "passive"))
      (node (ref "FB2") (pin "2") (pinfunction "2_2") (pintype "passive"))
      (node (ref "U4") (pin "21") (pinfunction "VREF+_21") (pintype "passive"))
      (node (ref "U4") (pin "22") (pinfunction "VDDA_22") (pintype "passive"))
    )
    (net (code "10") (name "/BOOT0") (class "Default")
      (node (ref "P20") (pin "2") (pinfunction "2_2") (pintype "passive"))
      (node (ref "U4") (pin "94") (pinfunction "BOOT0_94") (pintype "passive"))
    )
    (net (code "11") (name "/BUZZER") (class "Default")
      (node (ref "Q11") (pin "2") (pinfunction "G_2") (pintype "passive"))
      (node (ref "R32") (pin "2") (pinfunction "2_2") (pintype "passive"))
      (node (ref "U4") (pin "57") (pinfunction "PD10_57") (pintype "passive"))
    )
    (net (code "12") (name "/CS_FLH") (class "Default")
      (node (ref "U4") (pin "51") (pinfunction "PB12_51") (pintype "passive"))
      (node (ref "U7") (pin "1") (pinfunction "CS_1") (pintype "passive"))
    )
    (net (code "13") (name "/Chg_EN") (class "Default")
      (node (ref "R57") (pin "2") (pinfunction "2_2") (pintype "passive"))
      (node (ref "U4") (pin "23") (pinfunction "PA0-WKUP1_23") (pintype "passive"))
      (node (ref "U9") (pin "9") (pinfunction "~{CE}_9") (pintype "passive"))
    )
    (net (code "14") (name "/Chg_PG") (class "Default")
      (node (ref "U4") (pin "83") (pinfunction "PD2_83") (pintype "passive"))
      (node (ref "U9") (pin "7") (pinfunction "~{PG}_7") (pintype "passive"))
    )
    (net (code "15") (name "/D+") (class "Default")
      (node (ref "U9") (pin "3") (pinfunction "D+_3") (pintype "passive"))
    )
    (net (code "16") (name "/D-") (class "Default")
      (node (ref "U9") (pin "4") (pinfunction "D-_4") (pintype "passive"))
    )
    (net (code "17") (name "/GNSS_TXD") (class "Default")
      (node (ref "U5") (pin "22") (pinfunction "TXD_GNSS_22") (pintype "passive"))
      (node (ref "U6") (pin "3") (pinfunction "A2_3") (pintype "passive"))
    )
    (net (code "18") (name "/Green_LED") (class "Default")
      (node (ref "R48") (pin "1") (pinfunction "1_1") (pintype "passive"))
      (node (ref "U4") (pin "81") (pinfunction "PD0_81") (pintype "passive"))
    )
    (net (code "19") (name "/IEXC1") (class "Default")
      (node (ref "D20") (pin "2") (pinfunction "K_2") (pintype "passive"))
      (node (ref "D26") (pin "2") (pinfunction "K_2") (pintype "passive"))
      (node (ref "P1") (pin "6") (pinfunction "6_6") (pintype "passive"))
      (node (ref "P7") (pin "2") (pinfunction "2_2") (pintype "passive"))
      (node (ref "R15") (pin "2") (pinfunction "vs_2") (pintype "passive"))
      (node (ref "TP27") (pin "1") (pintype "passive"))
      (node (ref "U1") (pin "20") (pinfunction "IEXC1_20") (pintype "passive"))
    )
    (net (code "20") (name "/IEXC2") (class "Default")
      (node (ref "D17") (pin "2") (pinfunction "K_2") (pintype "passive"))
      (node (ref "P2") (pin "6") (pinfunction "6_6") (pintype "passive"))
      (node (ref "R16") (pin "2") (pinfunction "vs_2") (pintype "passive"))
      (node (ref "TP24") (pin "1") (pintype "passive"))
      (node (ref "U1") (pin "19") (pinfunction "IEXC2_19") (pintype "passive"))
    )
    (net (code "21") (name "/MCU_NB_RI") (class "Default")
      (node (ref "U4") (pin "68") (pinfunction "PA9_68") (pintype "passive"))
      (node (ref "U6") (pin "13") (pinfunction "B1_13") (pintype "passive"))
    )
    (net (code "22") (name "/MCU_RXD1") (class "Default")
      (node (ref "U4") (pin "69") (pinfunction "PA10_69") (pintype "passive"))
      (node (ref "U6") (pin "12") (pinfunction "B2_12") (pintype "passive"))
    )
    (net (code "23") (name "/MCU_RXD3") (class "Default")
      (node (ref "U4") (pin "79") (pinfunction "PC11_79") (pintype "passive"))
      (node (ref "U6") (pin "11") (pinfunction "B3_11") (pintype "passive"))
    )
    (net (code "24") (name "/MCU_TXD3") (class "Default")
      (node (ref "U4") (pin "78") (pinfunction "PC10_78") (pintype "passive"))
      (node (ref "U6") (pin "10") (pinfunction "B4_10") (pintype "passive"))
    )
    (net (code "25") (name "/MISO") (class "Default")
      (node (ref "U4") (pin "53") (pinfunction "PB14_53") (pintype "passive"))
      (node (ref "U7") (pin "2") (pinfunction "DO(IO1)_2") (pintype "passive"))
    )
    (net (code "26") (name "/MOSI") (class "Default")
      (node (ref "U4") (pin "54") (pinfunction "PB15_54") (pintype "passive"))
      (node (ref "U7") (pin "5") (pinfunction "DI(IO0)_5") (pintype "passive"))
    )
    (net (code "27") (name "/MPU_INT") (class "Default")
      (node (ref "U2") (pin "12") (pinfunction "INT_12") (pintype "passive"))
      (node (ref "U4") (pin "55") (pinfunction "PD8_55") (pintype "passive"))
    )
    (net (code "28") (name "/MPU_PWR_EN") (class "Default")
      (node (ref "U22") (pin "B2") (pinfunction "ON_B2") (pintype "passive"))
      (node (ref "U4") (pin "56") (pinfunction "PD9_56") (pintype "passive"))
    )
    (net (code "29") (name "/NB_NETLIGHT") (class "Default")
      (node (ref "U4") (pin "97") (pinfunction "PE0_97") (pintype "passive"))
      (node (ref "U5") (pin "47") (pinfunction "NETLIGHT_47") (pintype "passive"))
    )
    (net (code "30") (name "/NB_PWR_EN") (class "Default")
      (node (ref "U24") (pin "B2") (pinfunction "ON_B2") (pintype "passive"))
      (node (ref "U4") (pin "70") (pinfunction "PA11_70") (pintype "passive"))
    )
    (net (code "31") (name "/NB_PWR_KEY") (class "Default")
      (node (ref "TP1") (pin "1") (pintype "passive"))
      (node (ref "U5") (pin "5") (pinfunction "PWRKEY_5") (pintype "passive"))
    )
    (net (code "32") (name "/NB_RI") (class "Default")
      (node (ref "U5") (pin "35") (pinfunction "RI_35") (pintype "passive"))
      (node (ref "U6") (pin "2") (pinfunction "A1_2") (pintype "passive"))
    )
    (net (code "33") (name "/NB_RST") (class "Default")
      (node (ref "U4") (pin "80") (pinfunction "PC12_80") (pintype "passive"))
      (node (ref "U5") (pin "53") (pinfunction "RESET_53") (pintype "passive"))
    )
    (net (code "34") (name "/NB_RXD") (class "Default")
      (node (ref "U5") (pin "33") (pinfunction "RXD_33") (pintype "passive"))
      (node (ref "U6") (pin "5") (pinfunction "A4_5") (pintype "passive"))
    )
    (net (code "35") (name "/NB_TXD") (class "Default")
      (node (ref "U5") (pin "34") (pinfunction "TXD_34") (pintype "passive"))
      (node (ref "U6") (pin "4") (pinfunction "A3_4") (pintype "passive"))
    )
    (net (code "36") (name "/NB_WAKEUP") (class "Default")
      (node (ref "U4") (pin "71") (pinfunction "PA12_71") (pintype "passive"))
      (node (ref "U5") (pin "37") (pinfunction "PSM_EINT_37") (pintype "passive"))
    )
    (net (code "37") (name "/OTG") (class "Default")
      (node (ref "R44") (pin "2") (pinfunction "2_2") (pintype "passive"))
      (node (ref "U4") (pin "26") (pinfunction "PA3_26") (pintype "passive"))
      (node (ref "U9") (pin "6") (pinfunction "OTG_6") (pintype "passive"))
    )
    (net (code "38") (name "/REFN0") (class "Default")
      (node (ref "C20") (pin "2") (pinfunction "2_2") (pintype "passive"))
      (node (ref "C22") (pin "1") (pinfunction "1_1") (pintype "passive"))
      (node (ref "R29") (pin "1") (pinfunction "vs_1") (pintype "passive"))
      (node (ref "U1") (pin "6") (pinfunction "REFN0/GPIO1_6") (pintype "passive"))
    )
    (net (code "39") (name "/REFN1") (class "Default")
      (node (ref "C21") (pin "2") (pinfunction "2_2") (pintype "passive"))
      (node (ref "C23") (pin "1") (pinfunction "1_1") (pintype "passive"))
      (node (ref "R30") (pin "1") (pinfunction "vs_1") (pintype "passive"))
      (node (ref "U1") (pin "8") (pinfunction "REFN1_8") (pintype "passive"))
    )
    (net (code "40") (name "/REFP0") (class "Default")
      (node (ref "C16") (pin "1") (pinfunction "1_1") (pintype "passive"))
      (node (ref "C20") (pin "1") (pinfunction "1_1") (pintype "passive"))
      (node (ref "R23") (pin "1") (pinfunction "vs_1") (pintype "passive"))
      (node (ref "U1") (pin "5") (pinfunction "REFP0/GPIO0_5") (pintype "passive"))
    )
    (net (code "41") (name "/REFP1") (class "Default")
      (node (ref "C17") (pin "1") (pinfunction "1_1") (pintype "passive"))
      (node (ref "C21") (pin "1") (pinfunction "1_1") (pintype "passive"))
      (node (ref "R24") (pin "1") (pinfunction "vs_1") (pintype "passive"))
      (node (ref "U1") (pin "7") (pinfunction "REFP1_7") (pintype "passive"))
    )
    (net (code "42") (name "/REGN") (class "Default")
      (node (ref "C51") (pin "2") (pintype "passive"))
      (node (ref "R55") (pin "1") (pinfunction "1_1") (pintype "passive"))
      (node (ref "U9") (pin "22") (pinfunction "REGN_22") (pintype "passive"))
    )
    (net (code "43") (name "/REP1") (class "Default")
      (node (ref "D18") (pin "2") (pinfunction "K_2") (pintype "passive"))
      (node (ref "D25") (pin "2") (pinfunction "K_2") (pintype "passive"))
      (node (ref "P1") (pin "5") (pinfunction "5_5") (pintype "passive"))
      (node (ref "P7") (pin "1") (pinfunction "1_1") (pintype "passive"))
      (node (ref "R23") (pin "2") (pinfunction "vs_2") (pintype "passive"))
      (node (ref "R25") (pin "2") (pinfunction "2_2") (pintype "passive"))
      (node (ref "TP29") (pin "1") (pintype "passive"))
    )
    (net (code "44") (name "/REP2") (class "Default")
      (node (ref "D15") (pin "2") (pinfunction "K_2") (pintype "passive"))
      (node (ref "P2") (pin "5") (pinfunction "5_5") (pintype "passive"))
      (node (ref "R24") (pin "2") (pinfunction "vs_2") (pintype "passive"))
      (node (ref "R26") (pin "2") (pinfunction "2_2") (pintype "passive"))
      (node (ref "TP26") (pin "1") (pintype "passive"))
    )
    (net (code "45") (name "/RESET") (class "Default")
      (node (ref "C49") (pin "1") (pinfunction "1_1") (pintype "passive"))
      (node (ref "R43") (pin "1") (pinfunction "1_1") (pintype "passive"))
      (node (ref "U4") (pin "14") (pinfunction "NRST_14") (pintype "passive"))
    )
    (net (code "46") (name "/RTCK") (class "Default")
      (node (ref "J1") (pin "7") (pinfunction "7_7") (pintype "passive"))
      (node (ref "R41") (pin "1") (pinfunction "1_1") (pintype "passive"))
    )
    (net (code "47") (name "/RTCX1") (class "Default")
      (node (ref "C37") (pin "2") (pintype "passive"))
      (node (ref "U4") (pin "8") (pinfunction "PC14-OSC32_IN_8") (pintype "passive"))
      (node (ref "X2") (pin "2") (pintype "passive"))
    )
    (net (code "48") (name "/RTCX2") (class "Default")
      (node (ref "C39") (pin "2") (pintype "passive"))
      (node (ref "U4") (pin "9") (pinfunction "PC15-OSC32_OUT_9") (pintype "passive"))
      (node (ref "X2") (pin "1") (pintype "passive"))
    )
    (net (code "49") (name "/RTD1+") (class "Default")
      (node (ref "C11") (pin "1") (pinfunction "1_1") (pintype "passive"))
      (node (ref "C8") (pin "1") (pinfunction "1_1") (pintype "passive"))
      (node (ref "R15") (pin "1") (pinfunction "vs_1") (pintype "passive"))
      (node (ref "U1") (pin "16") (pinfunction "AIN7/IEXC/GPIO7_16") (pintype "passive"))
    )
    (net (code "50") (name "/RTD1-") (class "Default")
      (node (ref "C11") (pin "2") (pinfunction "2_2") (pintype "passive"))
      (node (ref "C13") (pin "1") (pinfunction "1_1") (pintype "passive"))
      (node (ref "R19") (pin "1") (pinfunction "vs_1") (pintype "passive"))
      (node (ref "U1") (pin "15") (pinfunction "AIN6/IEXC/GPIO6_15") (pintype "passive"))
    )
    (net (code "51") (name "/RTD2+") (class "Default")
      (node (ref "C12") (pin "1") (pinfunction "1_1") (pintype "passive"))
      (node (ref "C9") (pin "1") (pinfunction "1_1") (pintype "passive"))
      (node (ref "R16") (pin "1") (pinfunction "vs_1") (pintype "passive"))
      (node (ref "U1") (pin "13") (pinfunction "AIN4/IEXC/GPIO4_13") (pintype "passive"))
    )
    (net (code "52") (name "/RTD2-") (class "Default")
      (node (ref "C12") (pin "2") (pinfunction "2_2") (pintype "passive"))
      (node (ref "C14") (pin "1") (pinfunction "1_1") (pintype "passive"))
      (node (ref "R20") (pin "1") (pinfunction "vs_1") (pintype "passive"))
      (node (ref "U1") (pin "14") (pinfunction "AIN5/IEXC/GPIO5_14") (pintype "passive"))
    )
    (net (code "53") (name "/RXD2") (class "Default")
      (node (ref "D24") (pin "1") (pinfunction "A_1") (pintype "passive"))
      (node (ref "R28") (pin "1") (pinfunction "1_1") (pintype "passive"))
      (node (ref "U4") (pin "87") (pinfunction "PD6_87") (pintype "passive"))
    )
    (net (code "54") (name "/Red_LED") (class "Default")
      (node (ref "R47") (pin "1") (pinfunction "1_1") (pintype "passive"))
      (node (ref "U4") (pin "82") (pinfunction "PD1_82") (pintype "passive"))
    )
    (net (code "55") (name "/SCL3") (class "Default")
      (node (ref "P4") (pin "2") (pinfunction "2_2") (pintype "passive"))
      (node (ref "R12") (pin "2") (pinfunction "2_2") (pintype "passive"))
      (node (ref "R35") (pin "1") (pinfunction "1_1") (pintype "passive"))
      (node (ref "TP23") (pin "1") (pintype "passive"))
      (node (ref "U2") (pin "23") (pinfunction "SCL_23") (pintype "passive"))
      (node (ref "U4") (pin "95") (pinfunction "PB8_95") (pintype "passive"))
    )
    (net (code "56") (name "/SCL3-InHM") (class "Default")
      (node (ref "P5") (pin "2") (pinfunction "2_2") (pintype "passive"))
      (node (ref "U3") (pin "6") (pinfunction "SCL_6") (pintype "passive"))
    )
    (net (code "57") (name "/SCLK") (class "Default")
      (node (ref "U4") (pin "52") (pinfunction "PB13_52") (pintype "passive"))
      (node (ref "U7") (pin "6") (pinfunction "CLK_6") (pintype "passive"))
    )
    (net (code "58") (name "/SCL_ExHM1") (class "Default")
      (node (ref "D13") (pin "2") (pinfunction "K_2") (pintype "passive"))
      (node (ref "P1") (pin "4") (pinfunction "4_4") (pintype "passive"))
      (node (ref "R12") (pin "1") (pinfunction "1_1") (pintype "passive"))
      (node (ref "R3") (pin "1") (pinfunction "1_1") (pintype "passive"))
      (node (ref "TP17") (pin "1") (pintype "passive"))
    )
    (net (code "59") (name "/SCL_ExHM2") (class "Default")
      (node (ref "D11") (pin "2") (pinfunction "K_2") (pintype "passive"))
      (node (ref "P2") (pin "4") (pinfunction "4_4") (pintype "passive"))
      (node (ref "R11") (pin "1") (pinfunction "1_1") (pintype "passive"))
      (node (ref "R17") (pin "1") (pinfunction "1_1") (pintype "passive"))
      (node (ref "TP19") (pin "1") (pintype "passive"))
    )
    (net (code "60") (name "/SDA3") (class "Default")
      (node (ref "P4") (pin "1") (pinfunction "1_1") (pintype "passive"))
      (node (ref "R36") (pin "1") (pinfunction "1_1") (pintype "passive"))
      (node (ref "R4") (pin "2") (pinfunction "2_2") (pintype "passive"))
      (node (ref "TP22") (pin "1") (pintype "passive"))
      (node (ref "U2") (pin "24") (pinfunction "SDA_24") (pintype "passive"))
      (node (ref "U4") (pin "96") (pinfunction "PB9_96") (pintype "passive"))
    )
    (net (code "61") (name "/SDA3-InHM") (class "Default")
      (node (ref "P5") (pin "1") (pinfunction "1_1") (pintype "passive"))
      (node (ref "U3") (pin "1") (pinfunction "SDA_1") (pintype "passive"))
    )
    (net (code "62") (name "/SDA_ExHM1") (class "Default")
      (node (ref "D14") (pin "2") (pinfunction "K_2") (pintype "passive"))
      (node (ref "P1") (pin "3") (pinfunction "3_3") (pintype "passive"))
      (node (ref "R2") (pin "1") (pinfunction "1_1") (pintype "passive"))
      (node (ref "R4") (pin "1") (pinfunction "1_1") (pintype "passive"))
      (node (ref "TP16") (pin "1") (pintype "passive"))
    )
    (net (code "63") (name "/SDA_ExHM2") (class "Default")
      (node (ref "D12") (pin "2") (pinfunction "K_2") (pintype "passive"))
      (node (ref "P2") (pin "3") (pinfunction "3_3") (pintype "passive"))
      (node (ref "R10") (pin "1") (pinfunction "1_1") (pintype "passive"))
      (node (ref "R14") (pin "1") (pinfunction "1_1") (pintype "passive"))
      (node (ref "TP18") (pin "1") (pintype "passive"))
    )
    (net (code "64") (name "/SHT_PWR_EN") (class "Default")
      (node (ref "U21") (pin "B2") (pinfunction "ON_B2") (pintype "passive"))
      (node (ref "U4") (pin "58") (pinfunction "PD11_58") (pintype "passive"))
    )
    (net (code "65") (name "/SHT_SCL2") (class "Default")
      (node (ref "R17") (pin "2") (pinfunction "2_2") (pintype "passive"))
      (node (ref "U4") (pin "47") (pinfunction "PB10_47") (pintype "passive"))
    )
    (net (code "66") (name "/SHT_SDA2") (class "Default")
      (node (ref "R14") (pin "2") (pinfunction "2_2") (pintype "passive"))
      (node (ref "U4") (pin "48") (pinfunction "PB11_48") (pintype "passive"))
    )
    (net (code "67") (name "/SIM_CLK") (class "Default")
      (node (ref "R39") (pin "2") (pinfunction "2_2") (pintype "passive"))
      (node (ref "U5") (pin "19") (pinfunction "SIM_CLK_19") (pintype "passive"))
    )
    (net (code "68") (name "/SIM_DATA") (class "Default")
      (node (ref "R37") (pin "1") (pinfunction "1_1") (pintype "passive"))
      (node (ref "R38") (pin "2") (pinfunction "2_2") (pintype "passive"))
      (node (ref "U5") (pin "21") (pinfunction "SIM_DATA_21") (pintype "passive"))
    )
    (net (code "69") (name "/SIM_RST") (class "Default")
      (node (ref "R40") (pin "2") (pinfunction "2_2") (pintype "passive"))
      (node (ref "U5") (pin "20") (pinfunction "SIM_RST_20") (pintype "passive"))
    )
    (net (code "70") (name "/SWCLK") (class "Default")
      (node (ref "J1") (pin "2") (pinfunction "2_2") (pintype "passive"))
      (node (ref "R49") (pin "1") (pinfunction "1_1") (pintype "passive"))
      (node (ref "U4") (pin "76") (pinfunction "PA14_76") (pintype "passive"))
    )
    (net (code "71") (name "/SWDIO") (class "Default")
      (node (ref "J1") (pin "4") (pinfunction "4_4") (pintype "passive"))
      (node (ref "R33") (pin "1") (pinfunction "1_1") (pintype "passive"))
      (node (ref "U4") (pin "72") (pinfunction "PA13_72") (pintype "passive"))
    )
    (net (code "72") (name "/Snooze") (class "Default")
      (node (ref "R6") (pin "2") (pinfunction "2_2") (pintype "passive"))
      (node (ref "U10") (pin "3") (pinfunction "MODE_3") (pintype "passive"))
      (node (ref "U4") (pin "84") (pinfunction "PD3_84") (pintype "passive"))
    )
    (net (code "73") (name "/TAMPER") (class "Default")
      (node (ref "P6") (pin "4") (pinfunction "4_4") (pintype "passive"))
      (node (ref "R18") (pin "1") (pinfunction "1_1") (pintype "passive"))
      (node (ref "U4") (pin "65") (pinfunction "PC8_65") (pintype "passive"))
    )
    (net (code "74") (name "/TAMPER-s") (class "Default")
      (node (ref "C76") (pin "1") (pinfunction "1_1") (pintype "passive"))
      (node (ref "D22") (pin "2") (pinfunction "K_2") (pintype "passive"))
      (node (ref "P3") (pin "4") (pinfunction "4_4") (pintype "passive"))
      (node (ref "TP30") (pin "1") (pintype "passive"))
    )
    (net (code "75") (name "/TC1-") (class "Default")
      (node (ref "D19") (pin "2") (pinfunction "K_2") (pintype "passive"))
      (node (ref "D27") (pin "2") (pinfunction "K_2") (pintype "passive"))
      (node (ref "P1") (pin "7") (pinfunction "7_7") (pintype "passive"))
      (node (ref "P7") (pin "3") (pinfunction "3_3") (pintype "passive"))
      (node (ref "R19") (pin "2") (pinfunction "vs_2") (pintype "passive"))
      (node (ref "TP28") (pin "1") (pintype "passive"))
    )
    (net (code "76") (name "/TC2-") (class "Default")
      (node (ref "D16") (pin "2") (pinfunction "K_2") (pintype "passive"))
      (node (ref "P2") (pin "7") (pinfunction "7_7") (pintype "passive"))
      (node (ref "R20") (pin "2") (pinfunction "vs_2") (pintype "passive"))
      (node (ref "TP25") (pin "1") (pintype "passive"))
    )
    (net (code "77") (name "/TDI") (class "Default")
      (node (ref "J1") (pin "5") (pinfunction "5_5") (pintype "passive"))
      (node (ref "R31") (pin "1") (pinfunction "1_1") (pintype "passive"))
      (node (ref "U4") (pin "77") (pinfunction "PA15_77") (pintype "passive"))
    )
    (net (code "78") (name "/TDO") (class "Default")
      (node (ref "J1") (pin "6") (pinfunction "6_6") (pintype "passive"))
      (node (ref "R46") (pin "1") (pinfunction "1_1") (pintype "passive"))
      (node (ref "U4") (pin "89") (pinfunction "PB3_89") (pintype "passive"))
    )
    (net (code "79") (name "/TFT_EN") (class "Default")
      (node (ref "U20") (pin "B2") (pinfunction "ON_B2") (pintype "passive"))
      (node (ref "U4") (pin "35") (pinfunction "PB0_35") (pintype "passive"))
    )
    (net (code "80") (name "/TFT_RESET") (class "Default")
      (node (ref "P18") (pin "3") (pinfunction "RESET_3") (pintype "passive"))
      (node (ref "U4") (pin "33") (pinfunction "PC4_33") (pintype "passive"))
    )
    (net (code "81") (name "/TFT_RS") (class "Default")
      (node (ref "P18") (pin "6") (pinfunction "RS_6") (pintype "passive"))
      (node (ref "U4") (pin "36") (pinfunction "PB1_36") (pintype "passive"))
    )
    (net (code "82") (name "/TFT_SDA1") (class "Default")
      (node (ref "P18") (pin "8") (pinfunction "SDA_8") (pintype "passive"))
      (node (ref "U4") (pin "32") (pinfunction "PA7_32") (pintype "passive"))
    )
    (net (code "83") (name "/TXD2") (class "Default")
      (node (ref "R27") (pin "2") (pinfunction "2_2") (pintype "passive"))
      (node (ref "U4") (pin "86") (pinfunction "PD5_86") (pintype "passive"))
    )
    (net (code "84") (name "/TestMode_en") (class "Default")
      (node (ref "TP13") (pin "1") (pintype "passive"))
      (node (ref "U4") (pin "85") (pinfunction "PD4_85") (pintype "passive"))
    )
    (net (code "85") (name "/USB_N") (class "Default")
      (node (ref "CON1") (pin "A7") (pinfunction "D-_A7") (pintype "passive"))
      (node (ref "CON1") (pin "B7") (pinfunction "D-_B7") (pintype "passive"))
      (node (ref "D9") (pin "3") (pinfunction "IO1_3") (pintype "passive"))
      (node (ref "TP12") (pin "1") (pintype "passive"))
      (node (ref "U8") (pin "2") (pinfunction "UD-_2") (pintype "passive"))
    )
    (net (code "86") (name "/USB_P") (class "Default")
      (node (ref "CON1") (pin "A6") (pinfunction "D+_A6") (pintype "passive"))
      (node (ref "CON1") (pin "B6") (pinfunction "D+_B6") (pintype "passive"))
      (node (ref "D9") (pin "2") (pinfunction "IO2_2") (pintype "passive"))
      (node (ref "TP11") (pin "1") (pintype "passive"))
      (node (ref "U8") (pin "1") (pinfunction "UD+_1") (pintype "passive"))
    )
    (net (code "87") (name "/VRTCBAT") (class "Default")
      (node (ref "C41") (pin "1") (pinfunction "1_1") (pintype "passive"))
      (node (ref "D3") (pin "2") (pinfunction "K_2") (pintype "passive"))
      (node (ref "U4") (pin "6") (pinfunction "VLCD_6") (pintype "passive"))
    )
    (net (code "88") (name "/Vbatt_chk") (class "Default")
      (node (ref "R54") (pin "2") (pinfunction "2_2") (pintype "passive"))
      (node (ref "R59") (pin "1") (pinfunction "1_1") (pintype "passive"))
      (node (ref "U4") (pin "25") (pinfunction "PA2_25") (pintype "passive"))
    )
    (net (code "89") (name "/Vbatt_chk_en") (class "Default")
      (node (ref "R59") (pin "2") (pinfunction "2_2") (pintype "passive"))
      (node (ref "U4") (pin "24") (pinfunction "PA1_24") (pintype "passive"))
    )
    (net (code "90") (name "/Vsys_in-s") (class "Default")
      (node (ref "P3") (pin "2") (pinfunction "2_2") (pintype "passive"))
      (node (ref "Q5") (pin "1") (pinfunction "S_1") (pintype "passive"))
    )
    (net (code "91") (name "/Vsys_out-s") (class "Default")
      (node (ref "C77") (pin "1") (pinfunction "1_1") (pintype "passive"))
      (node (ref "D23") (pin "2") (pinfunction "K_2") (pintype "passive"))
      (node (ref "P3") (pin "1") (pinfunction "1_1") (pintype "passive"))
      (node (ref "Q5") (pin "3") (pinfunction "D_3") (pintype "passive"))
      (node (ref "S3") (pin "1") (pinfunction "COMMON_1") (pintype "passive"))
      (node (ref "S3") (pin "2") (pinfunction "COMMON_2") (pintype "passive"))
    )
    (net (code "92") (name "/XTAL1") (class "Default")
      (node (ref "C36") (pin "2") (pintype "passive"))
      (node (ref "U4") (pin "12") (pinfunction "PH0-OSC_IN_12") (pintype "passive"))
      (node (ref "X1") (pin "2") (pintype "passive"))
    )
    (net (code "93") (name "/XTAL2") (class "Default")
      (node (ref "C38") (pin "2") (pintype "passive"))
      (node (ref "U4") (pin "13") (pinfunction "PH1-OSC_OUT_13") (pintype "passive"))
      (node (ref "X1") (pin "1") (pintype "passive"))
    )
    (net (code "94") (name "/nTRST") (class "Default")
      (node (ref "J1") (pin "3") (pinfunction "3_3") (pintype "passive"))
      (node (ref "R22") (pin "1") (pinfunction "1_1") (pintype "passive"))
      (node (ref "U4") (pin "90") (pinfunction "PB4_90") (pintype "passive"))
    )
    (net (code "95") (name "3.3V") (class "Default")
      (node (ref "BZ1") (pin "1") (pinfunction "1_1") (pintype "passive"))
      (node (ref "C1") (pin "1") (pinfunction "1_1") (pintype "passive"))
      (node (ref "C30") (pin "1") (pintype "passive"))
      (node (ref "C40") (pin "2") (pinfunction "2_2") (pintype "passive"))
      (node (ref "C42") (pin "1") (pinfunction "1_1") (pintype "passive"))
      (node (ref "C43") (pin "1") (pinfunction "1_1") (pintype "passive"))
      (node (ref "C44") (pin "1") (pinfunction "1_1") (pintype "passive"))
      (node (ref "C45") (pin "1") (pinfunction "1_1") (pintype "passive"))
      (node (ref "C46") (pin "1") (pinfunction "1_1") (pintype "passive"))
      (node (ref "C48") (pin "1") (pinfunction "1_1") (pintype "passive"))
      (node (ref "C69") (pin "1") (pintype "passive"))
      (node (ref "C70") (pin "1") (pintype "passive"))
      (node (ref "C78") (pin "1") (pinfunction "1_1") (pintype "passive"))
      (node (ref "D10") (pin "2") (pinfunction "K_2") (pintype "passive"))
      (node (ref "D5") (pin "2") (pinfunction "K_2") (pintype "passive"))
      (node (ref "FB2") (pin "1") (pinfunction "1_1") (pintype "passive"))
      (node (ref "J1") (pin "1") (pinfunction "1_1") (pintype "passive"))
      (node (ref "L3") (pin "2") (pinfunction "2_2") (pintype "passive"))
      (node (ref "P18") (pin "5") (pinfunction "SCK_5") (pintype "passive"))
      (node (ref "P20") (pin "1") (pinfunction "1_1") (pintype "passive"))
      (node (ref "P4") (pin "4") (pinfunction "4_4") (pintype "passive"))
      (node (ref "R18") (pin "2") (pinfunction "2_2") (pintype "passive"))
      (node (ref "R22") (pin "2") (pinfunction "2_2") (pintype "passive"))
      (node (ref "R28") (pin "2") (pinfunction "2_2") (pintype "passive"))
      (node (ref "R31") (pin "2") (pinfunction "2_2") (pintype "passive"))
      (node (ref "R33") (pin "2") (pinfunction "2_2") (pintype "passive"))
      (node (ref "R35") (pin "2") (pinfunction "2_2") (pintype "passive"))
      (node (ref "R36") (pin "2") (pinfunction "2_2") (pintype "passive"))
      (node (ref "R41") (pin "2") (pinfunction "2_2") (pintype "passive"))
      (node (ref "R43") (pin "2") (pinfunction "2_2") (pintype "passive"))
      (node (ref "R46") (pin "2") (pinfunction "2_2") (pintype "passive"))
      (node (ref "R56") (pin "1") (pinfunction "1_1") (pintype "passive"))
      (node (ref "R6") (pin "1") (pinfunction "1_1") (pintype "passive"))
      (node (ref "R9") (pin "1") (pinfunction "1_1") (pintype "passive"))
      (node (ref "R9") (pin "2") (pinfunction "2_2") (pintype "passive"))
      (node (ref "S2") (pin "1") (pinfunction "1_1") (pintype "passive"))
      (node (ref "S2") (pin "2") (pinfunction "2_2") (pintype "passive"))
      (node (ref "TP20") (pin "1") (pintype "passive"))
      (node (ref "U10") (pin "5") (pinfunction "VOS_5") (pintype "passive"))
      (node (ref "U20") (pin "A2") (pinfunction "VIN_A2") (pintype "passive"))
      (node (ref "U21") (pin "A2") (pinfunction "VIN_A2") (pintype "passive"))
      (node (ref "U22") (pin "A2") (pinfunction "VIN_A2") (pintype "passive"))
      (node (ref "U23") (pin "A2") (pinfunction "VIN_A2") (pintype "passive"))
      (node (ref "U24") (pin "A2") (pinfunction "VIN_A2") (pintype "passive"))
      (node (ref "U4") (pin "100") (pinfunction "VDD_3_100") (pintype "passive"))
      (node (ref "U4") (pin "11") (pinfunction "VDD_5_11") (pintype "passive"))
      (node (ref "U4") (pin "28") (pinfunction "VDD_4_28") (pintype "passive"))
      (node (ref "U4") (pin "30") (pinfunction "PA5_30") (pintype "passive"))
      (node (ref "U4") (pin "37") (pinfunction "PB2_37") (pintype "passive"))
      (node (ref "U4") (pin "50") (pinfunction "VDD_1_50") (pintype "passive"))
      (node (ref "U4") (pin "66") (pinfunction "PC9_66") (pintype "passive"))
      (node (ref "U4") (pin "75") (pinfunction "VDD_2_75") (pintype "passive"))
      (node (ref "U4") (pin "98") (pinfunction "PE1_98") (pintype "passive"))
      (node (ref "U7") (pin "3") (pinfunction "IO2_3") (pintype "passive"))
      (node (ref "U7") (pin "7") (pinfunction "IO3_7") (pintype "passive"))
      (node (ref "U7") (pin "8") (pinfunction "VCC_8") (pintype "passive"))
    )
    (net (code "96") (name "3.3V_1148") (class "Default")
      (node (ref "C2") (pin "1") (pinfunction "1_1") (pintype "passive"))
      (node (ref "FB1") (pin "2") (pinfunction "2_2") (pintype "passive"))
      (node (ref "R1") (pin "1") (pinfunction "1_1") (pintype "passive"))
      (node (ref "U1") (pin "1") (pinfunction "DVDD_1") (pintype "passive"))
      (node (ref "U23") (pin "A1") (pinfunction "VOUT_A1") (pintype "passive"))
    )
    (net (code "97") (name "3.3V_1148A") (class "Default")
      (node (ref "C4") (pin "1") (pinfunction "1_1") (pintype "passive"))
      (node (ref "C5") (pin "1") (pintype "passive"))
      (node (ref "FB1") (pin "1") (pinfunction "1_1") (pintype "passive"))
      (node (ref "U1") (pin "22") (pinfunction "AVDD_22") (pintype "passive"))
    )
    (net (code "98") (name "3.3V_ExHM") (class "Default")
      (node (ref "D1") (pin "2") (pinfunction "K_2") (pintype "passive"))
      (node (ref "D2") (pin "2") (pinfunction "K_2") (pintype "passive"))
      (node (ref "P1") (pin "1") (pinfunction "1_1") (pintype "passive"))
      (node (ref "P2") (pin "1") (pinfunction "1_1") (pintype "passive"))
      (node (ref "R10") (pin "2") (pinfunction "2_2") (pintype "passive"))
      (node (ref "R11") (pin "2") (pinfunction "2_2") (pintype "passive"))
      (node (ref "R2") (pin "2") (pinfunction "2_2") (pintype "passive"))
      (node (ref "R3") (pin "2") (pinfunction "2_2") (pintype "passive"))
      (node (ref "TP14") (pin "1") (pintype "passive"))
      (node (ref "U21") (pin "A1") (pinfunction "VOUT_A1") (pintype "passive"))
    )
    (net (code "99") (name "3.3V_InHM-a") (class "Default")
      (node (ref "C6") (pin "1") (pinfunction "1_1") (pintype "passive"))
      (node (ref "C7") (pin "2") (pinfunction "2_2") (pintype "passive"))
      (node (ref "P5") (pin "4") (pinfunction "4_4") (pintype "passive"))
      (node (ref "U3") (pin "5") (pinfunction "VDD_5") (pintype "passive"))
    )
    (net (code "100") (name "3.3V_MPU") (class "Default")
      (node (ref "C26") (pin "1") (pintype "passive"))
      (node (ref "C27") (pin "2") (pintype "passive"))
      (node (ref "U2") (pin "13") (pinfunction "VDD_13") (pintype "passive"))
      (node (ref "U2") (pin "8") (pinfunction "VLOGIC_8") (pintype "passive"))
      (node (ref "U22") (pin "A1") (pinfunction "VOUT_A1") (pintype "passive"))
    )
    (net (code "101") (name "3.3V_NB") (class "Default")
      (node (ref "C31") (pin "2") (pintype "passive"))
      (node (ref "C32") (pin "2") (pintype "passive"))
      (node (ref "C33") (pin "2") (pintype "passive"))
      (node (ref "C35") (pin "2") (pintype "passive"))
      (node (ref "U24") (pin "A1") (pinfunction "VOUT_A1") (pintype "passive"))
      (node (ref "U5") (pin "50") (pinfunction "VBAT_50") (pintype "passive"))
      (node (ref "U5") (pin "51") (pinfunction "VBAT_51") (pintype "passive"))
      (node (ref "U6") (pin "14") (pinfunction "VCCB_14") (pintype "passive"))
    )
    (net (code "102") (name "3.3V_ep") (class "Default")
      (node (ref "C60") (pin "1") (pinfunction "1_1") (pintype "passive"))
      (node (ref "C61") (pin "1") (pinfunction "1_1") (pintype "passive"))
      (node (ref "C62") (pin "1") (pinfunction "1_1") (pintype "passive"))
      (node (ref "P18") (pin "2") (pinfunction "VCC_2") (pintype "passive"))
      (node (ref "R88") (pin "2") (pinfunction "2_2") (pintype "passive"))
      (node (ref "U20") (pin "A1") (pinfunction "VOUT_A1") (pintype "passive"))
    )
    (net (code "103") (name "GND") (class "Default")
      (node (ref "BT1") (pin "3") (pinfunction "-_3") (pintype "passive"))
      (node (ref "BT1") (pin "4") (pintype "passive"))
      (node (ref "BT1") (pin "5") (pintype "passive"))
      (node (ref "C1") (pin "2") (pinfunction "2_2") (pintype "passive"))
      (node (ref "C10") (pin "1") (pintype "passive"))
      (node (ref "C13") (pin "2") (pinfunction "2_2") (pintype "passive"))
      (node (ref "C14") (pin "2") (pinfunction "2_2") (pintype "passive"))
      (node (ref "C15") (pin "1") (pintype "passive"))
      (node (ref "C16") (pin "2") (pinfunction "2_2") (pintype "passive"))
      (node (ref "C17") (pin "2") (pinfunction "2_2") (pintype "passive"))
      (node (ref "C18") (pin "1") (pintype "passive"))
      (node (ref "C19") (pin "1") (pintype "passive"))
      (node (ref "C2") (pin "2") (pinfunction "2_2") (pintype "passive"))
      (node (ref "C22") (pin "2") (pinfunction "2_2") (pintype "passive"))
      (node (ref "C23") (pin "2") (pinfunction "2_2") (pintype "passive"))
      (node (ref "C24") (pin "2") (pintype "passive"))
      (node (ref "C26") (pin "2") (pintype "passive"))
      (node (ref "C27") (pin "1") (pintype "passive"))
      (node (ref "C28") (pin "1") (pintype "passive"))
      (node (ref "C3") (pin "1") (pinfunction "1_1") (pintype "passive"))
      (node (ref "C30") (pin "2") (pintype "passive"))
      (node (ref "C31") (pin "1") (pintype "passive"))
      (node (ref "C32") (pin "1") (pintype "passive"))
      (node (ref "C33") (pin "1") (pintype "passive"))
      (node (ref "C34") (pin "2") (pintype "passive"))
      (node (ref "C35") (pin "1") (pintype "passive"))
      (node (ref "C36") (pin "1") (pintype "passive"))
      (node (ref "C37") (pin "1") (pintype "passive"))
      (node (ref "C38") (pin "1") (pintype "passive"))
      (node (ref "C39") (pin "1") (pintype "passive"))
      (node (ref "C4") (pin "2") (pinfunction "2_2") (pintype "passive"))
      (node (ref "C40") (pin "1") (pinfunction "1_1") (pintype "passive"))
      (node (ref "C41") (pin "2") (pinfunction "2_2") (pintype "passive"))
      (node (ref "C42") (pin "2") (pinfunction "2_2") (pintype "passive"))
      (node (ref "C43") (pin "2") (pinfunction "2_2") (pintype "passive"))
      (node (ref "C44") (pin "2") (pinfunction "2_2") (pintype "passive"))
      (node (ref "C45") (pin "2") (pinfunction "2_2") (pintype "passive"))
      (node (ref "C46") (pin "2") (pinfunction "2_2") (pintype "passive"))
      (node (ref "C47") (pin "2") (pinfunction "2_2") (pintype "passive"))
      (node (ref "C48") (pin "2") (pinfunction "2_2") (pintype "passive"))
      (node (ref "C49") (pin "2") (pinfunction "2_2") (pintype "passive"))
      (node (ref "C5") (pin "2") (pintype "passive"))
      (node (ref "C50") (pin "2") (pinfunction "2_2") (pintype "passive"))
      (node (ref "C51") (pin "1") (pintype "passive"))
      (node (ref "C52") (pin "2") (pintype "passive"))
      (node (ref "C53") (pin "1") (pintype "passive"))
      (node (ref "C54") (pin "2") (pintype "passive"))
      (node (ref "C55") (pin "1") (pintype "passive"))
      (node (ref "C59") (pin "2") (pintype "passive"))
      (node (ref "C60") (pin "2") (pinfunction "2_2") (pintype "passive"))
      (node (ref "C61") (pin "2") (pinfunction "2_2") (pintype "passive"))
      (node (ref "C62") (pin "2") (pinfunction "2_2") (pintype "passive"))
      (node (ref "C66") (pin "2") (pintype "passive"))
      (node (ref "C67") (pin "2") (pintype "passive"))
      (node (ref "C69") (pin "2") (pintype "passive"))
      (node (ref "C70") (pin "2") (pintype "passive"))
      (node (ref "C75") (pin "1") (pinfunction "1_1") (pintype "passive"))
      (node (ref "C78") (pin "2") (pinfunction "2_2") (pintype "passive"))
      (node (ref "C8") (pin "2") (pinfunction "2_2") (pintype "passive"))
      (node (ref "C9") (pin "2") (pinfunction "2_2") (pintype "passive"))
      (node (ref "CON1") (pin "A1_B12") (pinfunction "GND_A1_B12") (pintype "passive"))
      (node (ref "CON1") (pin "B1_A12") (pinfunction "GND_B1_A12") (pintype "passive"))
      (node (ref "D1") (pin "1") (pinfunction "A_1") (pintype "passive"))
      (node (ref "D11") (pin "1") (pinfunction "A_1") (pintype "passive"))
      (node (ref "D12") (pin "1") (pinfunction "A_1") (pintype "passive"))
      (node (ref "D13") (pin "1") (pinfunction "A_1") (pintype "passive"))
      (node (ref "D14") (pin "1") (pinfunction "A_1") (pintype "passive"))
      (node (ref "D15") (pin "1") (pinfunction "A_1") (pintype "passive"))
      (node (ref "D16") (pin "1") (pinfunction "A_1") (pintype "passive"))
      (node (ref "D17") (pin "1") (pinfunction "A_1") (pintype "passive"))
      (node (ref "D18") (pin "1") (pinfunction "A_1") (pintype "passive"))
      (node (ref "D19") (pin "1") (pinfunction "A_1") (pintype "passive"))
      (node (ref "D2") (pin "1") (pinfunction "A_1") (pintype "passive"))
      (node (ref "D20") (pin "1") (pinfunction "A_1") (pintype "passive"))
      (node (ref "D25") (pin "1") (pinfunction "A_1") (pintype "passive"))
      (node (ref "D26") (pin "1") (pinfunction "A_1") (pintype "passive"))
      (node (ref "D27") (pin "1") (pinfunction "A_1") (pintype "passive"))
      (node (ref "D5") (pin "1") (pinfunction "A_1") (pintype "passive"))
      (node (ref "J1") (pin "8") (pinfunction "8_8") (pintype "passive"))
      (node (ref "P1") (pin "2") (pinfunction "2_2") (pintype "passive"))
      (node (ref "P1") (pin "8") (pinfunction "8_8") (pintype "passive"))
      (node (ref "P1") (pin "9") (pinfunction "9_9") (pintype "passive"))
      (node (ref "P18") (pin "1") (pinfunction "GND_1") (pintype "passive"))
      (node (ref "P18") (pin "10") (pinfunction "LEDK_10") (pintype "passive"))
      (node (ref "P18") (pin "4") (pinfunction "CS_4") (pintype "passive"))
      (node (ref "P2") (pin "2") (pinfunction "2_2") (pintype "passive"))
      (node (ref "P2") (pin "8") (pinfunction "8_8") (pintype "passive"))
      (node (ref "P2") (pin "9") (pinfunction "9_9") (pintype "passive"))
      (node (ref "P20") (pin "3") (pinfunction "3_3") (pintype "passive"))
      (node (ref "P20") (pin "4") (pinfunction "4_4") (pintype "passive"))
      (node (ref "P20") (pin "5") (pinfunction "5_5") (pintype "passive"))
      (node (ref "P4") (pin "3") (pinfunction "3_3") (pintype "passive"))
      (node (ref "P4") (pin "5") (pinfunction "5_5") (pintype "passive"))
      (node (ref "P4") (pin "6") (pinfunction "6_6") (pintype "passive"))
      (node (ref "P6") (pin "3") (pinfunction "3_3") (pintype "passive"))
      (node (ref "P6") (pin "5") (pinfunction "5_5") (pintype "passive"))
      (node (ref "P6") (pin "6") (pinfunction "6_6") (pintype "passive"))
      (node (ref "P7") (pin "4") (pinfunction "4_4") (pintype "passive"))
      (node (ref "P7") (pin "5") (pinfunction "5_5") (pintype "passive"))
      (node (ref "PP2") (pin "1") (pintype "passive"))
      (node (ref "PP4") (pin "1") (pintype "passive"))
      (node (ref "R21") (pin "1") (pinfunction "1_1") (pintype "passive"))
      (node (ref "R25") (pin "1") (pinfunction "1_1") (pintype "passive"))
      (node (ref "R26") (pin "1") (pinfunction "1_1") (pintype "passive"))
      (node (ref "R29") (pin "2") (pinfunction "vs_2") (pintype "passive"))
      (node (ref "R30") (pin "2") (pinfunction "vs_2") (pintype "passive"))
      (node (ref "R32") (pin "1") (pinfunction "1_1") (pintype "passive"))
      (node (ref "R44") (pin "1") (pinfunction "1_1") (pintype "passive"))
      (node (ref "R45") (pin "1") (pinfunction "1_1") (pintype "passive"))
      (node (ref "R49") (pin "2") (pinfunction "2_2") (pintype "passive"))
      (node (ref "R51") (pin "1") (pinfunction "1_1") (pintype "passive"))
      (node (ref "R52") (pin "1") (pinfunction "1_1") (pintype "passive"))
      (node (ref "R57") (pin "1") (pinfunction "1_1") (pintype "passive"))
      (node (ref "R58") (pin "1") (pinfunction "1_1") (pintype "passive"))
      (node (ref "R68") (pin "1") (pinfunction "1_1") (pintype "passive"))
      (node (ref "R69") (pin "1") (pinfunction "1_1") (pintype "passive"))
      (node (ref "R75") (pin "1") (pinfunction "1_1") (pintype "passive"))
      (node (ref "S2") (pin "3") (pinfunction "3_3") (pintype "passive"))
      (node (ref "S2") (pin "4") (pinfunction "4_4") (pintype "passive"))
      (node (ref "TP15") (pin "1") (pintype "passive"))
      (node (ref "TP21") (pin "1") (pintype "passive"))
      (node (ref "TP5") (pin "1") (pintype "passive"))
      (node (ref "TP6") (pin "1") (pintype "passive"))
      (node (ref "TVS5") (pin "1") (pinfunction "A_1") (pintype "passive"))
      (node (ref "U1") (pin "10") (pinfunction "VREFCOM_10") (pintype "passive"))
      (node (ref "U1") (pin "2") (pinfunction "DGND_2") (pintype "passive"))
      (node (ref "U1") (pin "21") (pinfunction "AVSS_21") (pintype "passive"))
      (node (ref "U1") (pin "3") (pinfunction "CLK_3") (pintype "passive"))
      (node (ref "U10") (pin "2") (pinfunction "GND_2") (pintype "passive"))
      (node (ref "U10") (pin "9") (pinfunction "TP_9") (pintype "passive"))
      (node (ref "U2") (pin "1") (pinfunction "CLKIN_1") (pintype "passive"))
      (node (ref "U2") (pin "11") (pinfunction "FSYNC_11") (pintype "passive"))
      (node (ref "U2") (pin "18") (pinfunction "GND_18") (pintype "passive"))
      (node (ref "U2") (pin "25") (pinfunction "TP_25") (pintype "passive"))
      (node (ref "U2") (pin "9") (pinfunction "AD0_9") (pintype "passive"))
      (node (ref "U20") (pin "B1") (pinfunction "GND_B1") (pintype "passive"))
      (node (ref "U21") (pin "B1") (pinfunction "GND_B1") (pintype "passive"))
      (node (ref "U22") (pin "B1") (pinfunction "GND_B1") (pintype "passive"))
      (node (ref "U23") (pin "B1") (pinfunction "GND_B1") (pintype "passive"))
      (node (ref "U24") (pin "B1") (pinfunction "GND_B1") (pintype "passive"))
      (node (ref "U4") (pin "10") (pinfunction "VSS_5_10") (pintype "passive"))
      (node (ref "U4") (pin "19") (pinfunction "VSSA_19") (pintype "passive"))
      (node (ref "U4") (pin "20") (pinfunction "VREF-_20") (pintype "passive"))
      (node (ref "U4") (pin "27") (pinfunction "VSS_4_27") (pintype "passive"))
      (node (ref "U4") (pin "29") (pinfunction "PA4_29") (pintype "passive"))
      (node (ref "U4") (pin "49") (pinfunction "VSS_1_49") (pintype "passive"))
      (node (ref "U4") (pin "74") (pinfunction "VSS_2_74") (pintype "passive"))
      (node (ref "U4") (pin "99") (pinfunction "VSS_3_99") (pintype "passive"))
      (node (ref "U5") (pin "14") (pinfunction "GND_14") (pintype "passive"))
      (node (ref "U5") (pin "27") (pinfunction "GND_27") (pintype "passive"))
      (node (ref "U5") (pin "31") (pinfunction "GND_31") (pintype "passive"))
      (node (ref "U5") (pin "40") (pinfunction "GND_40") (pintype "passive"))
      (node (ref "U5") (pin "42") (pinfunction "GND_42") (pintype "passive"))
      (node (ref "U5") (pin "44") (pinfunction "GND_44") (pintype "passive"))
      (node (ref "U5") (pin "45") (pinfunction "GND_45") (pintype "passive"))
      (node (ref "U5") (pin "48") (pinfunction "GND_48") (pintype "passive"))
      (node (ref "U5") (pin "49") (pinfunction "GND_49") (pintype "passive"))
      (node (ref "U6") (pin "15") (pinfunction "15_15") (pintype "passive"))
      (node (ref "U6") (pin "7") (pinfunction "GND_7") (pintype "passive"))
      (node (ref "U7") (pin "4") (pinfunction "GND_4") (pintype "passive"))
      (node (ref "U8") (pin "3") (pinfunction "GND_3") (pintype "passive"))
      (node (ref "U9") (pin "17") (pinfunction "GND_17") (pintype "passive"))
      (node (ref "U9") (pin "18") (pinfunction "GND_18") (pintype "passive"))
      (node (ref "U9") (pin "25") (pinfunction "TP_25") (pintype "passive"))
    )
    (net (code "104") (name "GND-InHM") (class "Default")
      (node (ref "C6") (pin "2") (pinfunction "2_2") (pintype "passive"))
      (node (ref "C7") (pin "1") (pinfunction "1_1") (pintype "passive"))
      (node (ref "P5") (pin "3") (pinfunction "3_3") (pintype "passive"))
      (node (ref "P5") (pin "5") (pinfunction "5_5") (pintype "passive"))
      (node (ref "P5") (pin "6") (pinfunction "6_6") (pintype "passive"))
      (node (ref "U3") (pin "2") (pinfunction "VSS_2") (pintype "passive"))
    )
    (net (code "105") (name "GND-s") (class "Default")
      (node (ref "C76") (pin "2") (pinfunction "2_2") (pintype "passive"))
      (node (ref "D22") (pin "1") (pinfunction "A_1") (pintype "passive"))
      (node (ref "P3") (pin "3") (pinfunction "3_3") (pintype "passive"))
      (node (ref "P3") (pin "5") (pinfunction "5_5") (pintype "passive"))
      (node (ref "P3") (pin "6") (pinfunction "6_6") (pintype "passive"))
      (node (ref "R13") (pin "1") (pinfunction "1_1") (pintype "passive"))
      (node (ref "TP31") (pin "1") (pintype "passive"))
    )
    (net (code "106") (name "Net-(BT1-+)") (class "Default")
      (node (ref "BT1") (pin "1") (pinfunction "+_1") (pintype "passive"))
      (node (ref "C59") (pin "1") (pintype "passive"))
      (node (ref "R54") (pin "1") (pinfunction "1_1") (pintype "passive"))
      (node (ref "R74") (pin "2") (pinfunction "2_2") (pintype "passive"))
      (node (ref "U9") (pin "13") (pinfunction "BAT_13") (pintype "passive"))
      (node (ref "U9") (pin "14") (pinfunction "BAT_14") (pintype "passive"))
    )
    (net (code "107") (name "Net-(BT1-T)") (class "Default")
      (node (ref "BT1") (pin "2") (pinfunction "T_2") (pintype "passive"))
      (node (ref "R55") (pin "2") (pinfunction "2_2") (pintype "passive"))
      (node (ref "R58") (pin "2") (pinfunction "2_2") (pintype "passive"))
      (node (ref "U9") (pin "11") (pinfunction "TS_11") (pintype "passive"))
    )
    (net (code "108") (name "Net-(C15-Pad2)") (class "Default")
      (node (ref "C15") (pin "2") (pintype "passive"))
      (node (ref "L4") (pin "2") (pinfunction "2_2") (pintype "passive"))
      (node (ref "PP3") (pin "1") (pintype "passive"))
    )
    (net (code "109") (name "Net-(C18-Pad2)") (class "Default")
      (node (ref "C18") (pin "2") (pintype "passive"))
      (node (ref "L5") (pin "1") (pinfunction "1_1") (pintype "passive"))
      (node (ref "PP1") (pin "1") (pintype "passive"))
    )
    (net (code "110") (name "Net-(C56-Pad1)") (class "Default")
      (node (ref "C56") (pin "1") (pintype "passive"))
      (node (ref "L1") (pin "1") (pinfunction "1_1") (pintype "passive"))
      (node (ref "U9") (pin "19") (pinfunction "SW_19") (pintype "passive"))
      (node (ref "U9") (pin "20") (pinfunction "SW_20") (pintype "passive"))
    )
    (net (code "111") (name "Net-(CON1-CC1)") (class "Default")
      (node (ref "CON1") (pin "A5") (pinfunction "CC1_A5") (pintype "passive"))
      (node (ref "R69") (pin "2") (pinfunction "2_2") (pintype "passive"))
    )
    (net (code "112") (name "Net-(CON1-CC2)") (class "Default")
      (node (ref "CON1") (pin "B5") (pinfunction "CC2_B5") (pintype "passive"))
      (node (ref "R68") (pin "2") (pinfunction "2_2") (pintype "passive"))
    )
    (net (code "113") (name "Net-(D3-A)") (class "Default")
      (node (ref "D3") (pin "1") (pinfunction "A_1") (pintype "passive"))
      (node (ref "R53") (pin "1") (pinfunction "1_1") (pintype "passive"))
      (node (ref "R56") (pin "2") (pinfunction "2_2") (pintype "passive"))
    )
    (net (code "114") (name "Net-(D4-Pad1)") (class "Default")
      (node (ref "D4") (pin "1") (pinfunction "1_1") (pintype "passive"))
      (node (ref "R48") (pin "2") (pinfunction "2_2") (pintype "passive"))
    )
    (net (code "115") (name "Net-(D4-Pad2)") (class "Default")
      (node (ref "D4") (pin "2") (pinfunction "2_2") (pintype "passive"))
      (node (ref "R47") (pin "2") (pinfunction "2_2") (pintype "passive"))
      (node (ref "R50") (pin "1") (pinfunction "1_1") (pintype "passive"))
    )
    (net (code "116") (name "Net-(D9-GND)") (class "Default")
      (node (ref "C55") (pin "2") (pintype "passive"))
      (node (ref "CON1") (pin "1") (pintype "passive"))
      (node (ref "CON1") (pin "2") (pintype "passive"))
      (node (ref "CON1") (pin "3") (pintype "passive"))
      (node (ref "CON1") (pin "4") (pintype "passive"))
      (node (ref "D9") (pin "1") (pinfunction "GND_1") (pintype "passive"))
      (node (ref "R21") (pin "2") (pinfunction "2_2") (pintype "passive"))
    )
    (net (code "117") (name "Net-(D10-A)") (class "Default")
      (node (ref "BZ1") (pin "2") (pinfunction "2_2") (pintype "passive"))
      (node (ref "D10") (pin "1") (pinfunction "A_1") (pintype "passive"))
      (node (ref "Q11") (pin "1") (pinfunction "D_1") (pintype "passive"))
    )
    (net (code "118") (name "Net-(D23-A)") (class "Default")
      (node (ref "C77") (pin "2") (pinfunction "2_2") (pintype "passive"))
      (node (ref "D23") (pin "1") (pinfunction "A_1") (pintype "passive"))
      (node (ref "Q5") (pin "2") (pinfunction "G_2") (pintype "passive"))
      (node (ref "R13") (pin "2") (pinfunction "2_2") (pintype "passive"))
      (node (ref "S3") (pin "3") (pinfunction "NO_3") (pintype "passive"))
      (node (ref "S3") (pin "4") (pinfunction "NO_4") (pintype "passive"))
    )
    (net (code "119") (name "Net-(D24-K)") (class "Default")
      (node (ref "D24") (pin "2") (pinfunction "K_2") (pintype "passive"))
      (node (ref "U8") (pin "8") (pinfunction "TXD_8") (pintype "passive"))
    )
    (net (code "120") (name "Net-(P18-LEDA)") (class "Default")
      (node (ref "P18") (pin "9") (pinfunction "LEDA_9") (pintype "passive"))
      (node (ref "R88") (pin "1") (pinfunction "1_1") (pintype "passive"))
    )
    (net (code "121") (name "Net-(Q11-S)") (class "Default")
      (node (ref "Q11") (pin "3") (pinfunction "S_3") (pintype "passive"))
      (node (ref "R75") (pin "2") (pinfunction "2_2") (pintype "passive"))
    )
    (net (code "122") (name "Net-(SIM1-CLK)") (class "Default")
      (node (ref "R39") (pin "1") (pinfunction "1_1") (pintype "passive"))
      (node (ref "SIM1") (pin "6") (pinfunction "CLK_6") (pintype "passive"))
    )
    (net (code "123") (name "Net-(SIM1-DATA)") (class "Default")
      (node (ref "R38") (pin "1") (pinfunction "1_1") (pintype "passive"))
      (node (ref "SIM1") (pin "3") (pinfunction "DATA_3") (pintype "passive"))
    )
    (net (code "124") (name "Net-(SIM1-RST)") (class "Default")
      (node (ref "R40") (pin "1") (pinfunction "1_1") (pintype "passive"))
      (node (ref "SIM1") (pin "7") (pinfunction "RST_7") (pintype "passive"))
    )
    (net (code "125") (name "Net-(U1-VREFOUT)") (class "Default")
      (node (ref "C3") (pin "2") (pinfunction "2_2") (pintype "passive"))
      (node (ref "U1") (pin "9") (pinfunction "VREFOUT_9") (pintype "passive"))
    )
    (net (code "126") (name "Net-(U2-CPOUT)") (class "Default")
      (node (ref "C24") (pin "1") (pintype "passive"))
      (node (ref "U2") (pin "20") (pinfunction "CPOUT_20") (pintype "passive"))
    )
    (net (code "127") (name "Net-(U2-REGOUT)") (class "Default")
      (node (ref "C28") (pin "2") (pintype "passive"))
      (node (ref "U2") (pin "10") (pinfunction "REGOUT_10") (pintype "passive"))
    )
    (net (code "128") (name "Net-(U5-GNSS_ANT)") (class "Default")
      (node (ref "C19") (pin "2") (pintype "passive"))
      (node (ref "L5") (pin "2") (pinfunction "2_2") (pintype "passive"))
      (node (ref "U5") (pin "15") (pinfunction "GNSS_ANT_15") (pintype "passive"))
    )
    (net (code "129") (name "Net-(U5-RF_ANT)") (class "Default")
      (node (ref "C10") (pin "2") (pintype "passive"))
      (node (ref "L4") (pin "1") (pinfunction "1_1") (pintype "passive"))
      (node (ref "U5") (pin "41") (pinfunction "RF_ANT_41") (pintype "passive"))
    )
    (net (code "130") (name "Net-(U5-RXD_DBG)") (class "Default")
      (node (ref "TP2") (pin "1") (pintype "passive"))
      (node (ref "U5") (pin "30") (pinfunction "RXD_DBG_30") (pintype "passive"))
    )
    (net (code "131") (name "Net-(U5-TXD_DBG)") (class "Default")
      (node (ref "TP3") (pin "1") (pintype "passive"))
      (node (ref "U5") (pin "29") (pinfunction "TXD_DBG_29") (pintype "passive"))
    )
    (net (code "132") (name "Net-(U8-RXD)") (class "Default")
      (node (ref "R27") (pin "1") (pinfunction "1_1") (pintype "passive"))
      (node (ref "U8") (pin "9") (pinfunction "RXD_9") (pintype "passive"))
    )
    (net (code "133") (name "Net-(U8-V3)") (class "Default")
      (node (ref "C75") (pin "2") (pinfunction "2_2") (pintype "passive"))
      (node (ref "U8") (pin "10") (pinfunction "V3_10") (pintype "passive"))
    )
    (net (code "134") (name "Net-(U9-BTST)") (class "Default")
      (node (ref "C56") (pin "2") (pintype "passive"))
      (node (ref "U9") (pin "21") (pinfunction "BTST_21") (pintype "passive"))
    )
    (net (code "135") (name "Net-(U9-ICHG)") (class "Default")
      (node (ref "R52") (pin "2") (pinfunction "2_2") (pintype "passive"))
      (node (ref "U9") (pin "10") (pinfunction "ICHG_10") (pintype "passive"))
    )
    (net (code "136") (name "Net-(U9-ILIM)") (class "Default")
      (node (ref "R51") (pin "2") (pinfunction "2_2") (pintype "passive"))
      (node (ref "U9") (pin "8") (pinfunction "ILIM_8") (pintype "passive"))
    )
    (net (code "137") (name "Net-(U9-PMID)") (class "Default")
      (node (ref "C53") (pin "2") (pintype "passive"))
      (node (ref "U9") (pin "23") (pinfunction "PMID_23") (pintype "passive"))
    )
    (net (code "138") (name "Net-(U9-STAT)") (class "Default")
      (node (ref "R50") (pin "2") (pinfunction "2_2") (pintype "passive"))
      (node (ref "U9") (pin "5") (pinfunction "STAT_5") (pintype "passive"))
    )
    (net (code "139") (name "Net-(U9-VSET)") (class "Default")
      (node (ref "R45") (pin "2") (pinfunction "2_2") (pintype "passive"))
      (node (ref "U9") (pin "12") (pinfunction "VSET_12") (pintype "passive"))
    )
    (net (code "140") (name "Net-(U10-SW)") (class "Default")
      (node (ref "L3") (pin "1") (pinfunction "1_1") (pintype "passive"))
      (node (ref "U10") (pin "7") (pinfunction "SW_7") (pintype "passive"))
    )
    (net (code "141") (name "SIM_GND") (class "Default")
      (node (ref "C29") (pin "1") (pinfunction "1_1") (pintype "passive"))
      (node (ref "SIM1") (pin "1") (pinfunction "GND_1") (pintype "passive"))
      (node (ref "U5") (pin "16") (pinfunction "SIM_GND_16") (pintype "passive"))
    )
    (net (code "142") (name "SIM_VDD") (class "Default")
      (node (ref "C29") (pin "2") (pinfunction "2_2") (pintype "passive"))
      (node (ref "R37") (pin "2") (pinfunction "2_2") (pintype "passive"))
      (node (ref "SIM1") (pin "8") (pinfunction "VCC_8") (pintype "passive"))
      (node (ref "U5") (pin "18") (pinfunction "SIM_VDD_18") (pintype "passive"))
    )
    (net (code "143") (name "VBUS") (class "Default")
      (node (ref "C50") (pin "1") (pinfunction "1_1") (pintype "passive"))
      (node (ref "C52") (pin "1") (pintype "passive"))
      (node (ref "C66") (pin "1") (pintype "passive"))
      (node (ref "CON1") (pin "A4_B9") (pinfunction "VBUS_A4_B9") (pintype "passive"))
      (node (ref "CON1") (pin "B4_A9") (pinfunction "VBUS_B4_A9") (pintype "passive"))
      (node (ref "TP4") (pin "1") (pintype "passive"))
      (node (ref "TVS5") (pin "2") (pinfunction "K_2") (pintype "passive"))
      (node (ref "U8") (pin "7") (pinfunction "VCC_7") (pintype "passive"))
      (node (ref "U9") (pin "1") (pinfunction "VAC_1") (pintype "passive"))
      (node (ref "U9") (pin "24") (pinfunction "VBUS_24") (pintype "passive"))
    )
    (net (code "144") (name "VDD_EXT_1V8") (class "Default")
      (node (ref "C34") (pin "1") (pintype "passive"))
      (node (ref "U5") (pin "43") (pinfunction "VDD_EXT_43") (pintype "passive"))
      (node (ref "U6") (pin "1") (pinfunction "VCCA_1") (pintype "passive"))
      (node (ref "U6") (pin "8") (pinfunction "OE_8") (pintype "passive"))
    )
    (net (code "145") (name "Vsys_in") (class "Default")
      (node (ref "C67") (pin "1") (pintype "passive"))
      (node (ref "P6") (pin "2") (pinfunction "2_2") (pintype "passive"))
      (node (ref "TP34") (pin "1") (pintype "passive"))
      (node (ref "U10") (pin "1") (pinfunction "EN_1") (pintype "passive"))
      (node (ref "U10") (pin "8") (pinfunction "VIN_8") (pintype "passive"))
    )
    (net (code "146") (name "Vsys_out") (class "Default")
      (node (ref "C54") (pin "1") (pintype "passive"))
      (node (ref "D4") (pin "3") (pinfunction "3_3") (pintype "passive"))
      (node (ref "D4") (pin "4") (pinfunction "4_4") (pintype "passive"))
      (node (ref "L1") (pin "2") (pinfunction "2_2") (pintype "passive"))
      (node (ref "P6") (pin "1") (pinfunction "1_1") (pintype "passive"))
      (node (ref "R53") (pin "2") (pinfunction "2_2") (pintype "passive"))
      (node (ref "R74") (pin "1") (pinfunction "1_1") (pintype "passive"))
      (node (ref "TP35") (pin "1") (pintype "passive"))
      (node (ref "U9") (pin "15") (pinfunction "SYS_15") (pintype "passive"))
      (node (ref "U9") (pin "16") (pinfunction "SYS_16") (pintype "passive"))
    )
    (net (code "147") (name "unconnected-(CON1-SBU1-PadA8)") (class "Default")
      (node (ref "CON1") (pin "A8") (pinfunction "SBU1_A8") (pintype "passive"))
    )
    (net (code "148") (name "unconnected-(CON1-SBU2-PadB8)") (class "Default")
      (node (ref "CON1") (pin "B8") (pinfunction "SBU2_B8") (pintype "passive"))
    )
    (net (code "149") (name "unconnected-(P18-NC-Pad7)") (class "Default")
      (node (ref "P18") (pin "7") (pinfunction "NC_7") (pintype "passive"))
    )
    (net (code "150") (name "unconnected-(SIM1-NC-Pad2)") (class "Default")
      (node (ref "SIM1") (pin "2") (pinfunction "NC_2") (pintype "passive"))
    )
    (net (code "151") (name "unconnected-(SIM1-NC-Pad4)") (class "Default")
      (node (ref "SIM1") (pin "4") (pinfunction "NC_4") (pintype "passive"))
    )
    (net (code "152") (name "unconnected-(SIM1-NC-Pad5)") (class "Default")
      (node (ref "SIM1") (pin "5") (pinfunction "NC_5") (pintype "passive"))
    )
    (net (code "153") (name "unconnected-(U1-AIN0{slash}IEXC-Pad11)") (class "Default")
      (node (ref "U1") (pin "11") (pinfunction "AIN0/IEXC_11") (pintype "passive"))
    )
    (net (code "154") (name "unconnected-(U1-AIN1{slash}IEXC-Pad12)") (class "Default")
      (node (ref "U1") (pin "12") (pinfunction "AIN1/IEXC_12") (pintype "passive"))
    )
    (net (code "155") (name "unconnected-(U1-AIN2{slash}IEXC{slash}GPIO2-Pad17)") (class "Default")
      (node (ref "U1") (pin "17") (pinfunction "AIN2/IEXC/GPIO2_17") (pintype "passive"))
    )
    (net (code "156") (name "unconnected-(U1-AIN3{slash}IEXC{slash}GPIO3-Pad18)") (class "Default")
      (node (ref "U1") (pin "18") (pinfunction "AIN3/IEXC/GPIO3_18") (pintype "passive"))
    )
    (net (code "157") (name "unconnected-(U2-AUX_CL-Pad7)") (class "Default")
      (node (ref "U2") (pin "7") (pinfunction "AUX_CL_7") (pintype "passive"))
    )
    (net (code "158") (name "unconnected-(U2-AUX_DA-Pad6)") (class "Default")
      (node (ref "U2") (pin "6") (pinfunction "AUX_DA_6") (pintype "passive"))
    )
    (net (code "159") (name "unconnected-(U2-NC-Pad2)") (class "Default")
      (node (ref "U2") (pin "2") (pinfunction "NC_2") (pintype "passive"))
    )
    (net (code "160") (name "unconnected-(U2-NC-Pad3)") (class "Default")
      (node (ref "U2") (pin "3") (pinfunction "NC_3") (pintype "passive"))
    )
    (net (code "161") (name "unconnected-(U2-NC-Pad4)") (class "Default")
      (node (ref "U2") (pin "4") (pinfunction "NC_4") (pintype "passive"))
    )
    (net (code "162") (name "unconnected-(U2-NC-Pad5)") (class "Default")
      (node (ref "U2") (pin "5") (pinfunction "NC_5") (pintype "passive"))
    )
    (net (code "163") (name "unconnected-(U2-NC-Pad14)") (class "Default")
      (node (ref "U2") (pin "14") (pinfunction "NC_14") (pintype "passive"))
    )
    (net (code "164") (name "unconnected-(U2-NC-Pad15)") (class "Default")
      (node (ref "U2") (pin "15") (pinfunction "NC_15") (pintype "passive"))
    )
    (net (code "165") (name "unconnected-(U2-NC-Pad16)") (class "Default")
      (node (ref "U2") (pin "16") (pinfunction "NC_16") (pintype "passive"))
    )
    (net (code "166") (name "unconnected-(U2-NC-Pad17)") (class "Default")
      (node (ref "U2") (pin "17") (pinfunction "NC_17") (pintype "passive"))
    )
    (net (code "167") (name "unconnected-(U2-RESV-Pad19)") (class "Default")
      (node (ref "U2") (pin "19") (pinfunction "RESV_19") (pintype "passive"))
    )
    (net (code "168") (name "unconnected-(U2-RESV-Pad21)") (class "Default")
      (node (ref "U2") (pin "21") (pinfunction "RESV_21") (pintype "passive"))
    )
    (net (code "169") (name "unconnected-(U2-RESV-Pad22)") (class "Default")
      (node (ref "U2") (pin "22") (pinfunction "RESV_22") (pintype "passive"))
    )
    (net (code "170") (name "unconnected-(U3-GND-Pad7)") (class "Default")
      (node (ref "U3") (pin "7") (pinfunction "GND_7") (pintype "passive"))
    )
    (net (code "171") (name "unconnected-(U3-NC-Pad3)") (class "Default")
      (node (ref "U3") (pin "3") (pinfunction "NC_3") (pintype "passive"))
    )
    (net (code "172") (name "unconnected-(U3-NC-Pad4)") (class "Default")
      (node (ref "U3") (pin "4") (pinfunction "NC_4") (pintype "passive"))
    )
    (net (code "173") (name "unconnected-(U4-PA6-Pad31)") (class "Default")
      (node (ref "U4") (pin "31") (pinfunction "PA6_31") (pintype "passive"))
    )
    (net (code "174") (name "unconnected-(U4-PA8-Pad67)") (class "Default")
      (node (ref "U4") (pin "67") (pinfunction "PA8_67") (pintype "passive"))
    )
    (net (code "175") (name "unconnected-(U4-PB5-Pad91)") (class "Default")
      (node (ref "U4") (pin "91") (pinfunction "PB5_91") (pintype "passive"))
    )
    (net (code "176") (name "unconnected-(U4-PB6-Pad92)") (class "Default")
      (node (ref "U4") (pin "92") (pinfunction "PB6_92") (pintype "passive"))
    )
    (net (code "177") (name "unconnected-(U4-PB7-Pad93)") (class "Default")
      (node (ref "U4") (pin "93") (pinfunction "PB7_93") (pintype "passive"))
    )
    (net (code "178") (name "unconnected-(U4-PC0-Pad15)") (class "Default")
      (node (ref "U4") (pin "15") (pinfunction "PC0_15") (pintype "passive"))
    )
    (net (code "179") (name "unconnected-(U4-PC1-Pad16)") (class "Default")
      (node (ref "U4") (pin "16") (pinfunction "PC1_16") (pintype "passive"))
    )
    (net (code "180") (name "unconnected-(U4-PC2-Pad17)") (class "Default")
      (node (ref "U4") (pin "17") (pinfunction "PC2_17") (pintype "passive"))
    )
    (net (code "181") (name "unconnected-(U4-PC3-Pad18)") (class "Default")
      (node (ref "U4") (pin "18") (pinfunction "PC3_18") (pintype "passive"))
    )
    (net (code "182") (name "unconnected-(U4-PC5-Pad34)") (class "Default")
      (node (ref "U4") (pin "34") (pinfunction "PC5_34") (pintype "passive"))
    )
    (net (code "183") (name "unconnected-(U4-PC6-Pad63)") (class "Default")
      (node (ref "U4") (pin "63") (pinfunction "PC6_63") (pintype "passive"))
    )
    (net (code "184") (name "unconnected-(U4-PC7-Pad64)") (class "Default")
      (node (ref "U4") (pin "64") (pinfunction "PC7_64") (pintype "passive"))
    )
    (net (code "185") (name "unconnected-(U4-PC13-WKUP2-Pad7)") (class "Default")
      (node (ref "U4") (pin "7") (pinfunction "PC13-WKUP2_7") (pintype "passive"))
    )
    (net (code "186") (name "unconnected-(U4-PD7-Pad88)") (class "Default")
      (node (ref "U4") (pin "88") (pinfunction "PD7_88") (pintype "passive"))
    )
    (net (code "187") (name "unconnected-(U4-PD12-Pad59)") (class "Default")
      (node (ref "U4") (pin "59") (pinfunction "PD12_59") (pintype "passive"))
    )
    (net (code "188") (name "unconnected-(U4-PD13-Pad60)") (class "Default")
      (node (ref "U4") (pin "60") (pinfunction "PD13_60") (pintype "passive"))
    )
    (net (code "189") (name "unconnected-(U4-PD14-Pad61)") (class "Default")
      (node (ref "U4") (pin "61") (pinfunction "PD14_61") (pintype "passive"))
    )
    (net (code "190") (name "unconnected-(U4-PD15-Pad62)") (class "Default")
      (node (ref "U4") (pin "62") (pinfunction "PD15_62") (pintype "passive"))
    )
    (net (code "191") (name "unconnected-(U4-PE2-Pad1)") (class "Default")
      (node (ref "U4") (pin "1") (pinfunction "PE2_1") (pintype "passive"))
    )
    (net (code "192") (name "unconnected-(U4-PE3-Pad2)") (class "Default")
      (node (ref "U4") (pin "2") (pinfunction "PE3_2") (pintype "passive"))
    )
    (net (code "193") (name "unconnected-(U4-PE4-Pad3)") (class "Default")
      (node (ref "U4") (pin "3") (pinfunction "PE4_3") (pintype "passive"))
    )
    (net (code "194") (name "unconnected-(U4-PE5-Pad4)") (class "Default")
      (node (ref "U4") (pin "4") (pinfunction "PE5_4") (pintype "passive"))
    )
    (net (code "195") (name "unconnected-(U4-PE6-WKUP3-Pad5)") (class "Default")
      (node (ref "U4") (pin "5") (pinfunction "PE6-WKUP3_5") (pintype "passive"))
    )
    (net (code "196") (name "unconnected-(U4-PE7-Pad38)") (class "Default")
      (node (ref "U4") (pin "38") (pinfunction "PE7_38") (pintype "passive"))
    )
    (net (code "197") (name "unconnected-(U4-PH2-Pad73)") (class "Default")
      (node (ref "U4") (pin "73") (pinfunction "PH2_73") (pintype "passive"))
    )
    (net (code "198") (name "unconnected-(U5-1PPS-Pad17)") (class "Default")
      (node (ref "U5") (pin "17") (pinfunction "1PPS_17") (pintype "passive"))
    )
    (net (code "199") (name "unconnected-(U5-ADC-Pad6)") (class "Default")
      (node (ref "U5") (pin "6") (pinfunction "ADC_6") (pintype "passive"))
    )
    (net (code "200") (name "unconnected-(U5-CTS-Pad38)") (class "Default")
      (node (ref "U5") (pin "38") (pinfunction "CTS_38") (pintype "passive"))
    )
    (net (code "201") (name "unconnected-(U5-DCD-Pad36)") (class "Default")
      (node (ref "U5") (pin "36") (pinfunction "DCD_36") (pintype "passive"))
    )
    (net (code "202") (name "unconnected-(U5-Pad3)") (class "Default")
      (node (ref "U5") (pin "3") (pintype "passive"))
    )
    (net (code "203") (name "unconnected-(U5-Pad4)") (class "Default")
      (node (ref "U5") (pin "4") (pintype "passive"))
    )
    (net (code "204") (name "unconnected-(U5-Pad7)") (class "Default")
      (node (ref "U5") (pin "7") (pintype "passive"))
    )
    (net (code "205") (name "unconnected-(U5-Pad8)") (class "Default")
      (node (ref "U5") (pin "8") (pintype "passive"))
    )
    (net (code "206") (name "unconnected-(U5-Pad9)") (class "Default")
      (node (ref "U5") (pin "9") (pintype "passive"))
    )
    (net (code "207") (name "unconnected-(U5-Pad10)") (class "Default")
      (node (ref "U5") (pin "10") (pintype "passive"))
    )
    (net (code "208") (name "unconnected-(U5-Pad13)") (class "Default")
      (node (ref "U5") (pin "13") (pintype "passive"))
    )
    (net (code "209") (name "unconnected-(U5-Pad23)") (class "Default")
      (node (ref "U5") (pin "23") (pintype "passive"))
    )
    (net (code "210") (name "unconnected-(U5-Pad26)") (class "Default")
      (node (ref "U5") (pin "26") (pintype "passive"))
    )
    (net (code "211") (name "unconnected-(U5-Pad28)") (class "Default")
      (node (ref "U5") (pin "28") (pintype "passive"))
    )
    (net (code "212") (name "unconnected-(U5-Pad32)") (class "Default")
      (node (ref "U5") (pin "32") (pintype "passive"))
    )
    (net (code "213") (name "unconnected-(U5-Pad46)") (class "Default")
      (node (ref "U5") (pin "46") (pintype "passive"))
    )
    (net (code "214") (name "unconnected-(U5-Pad52)") (class "Default")
      (node (ref "U5") (pin "52") (pintype "passive"))
    )
    (net (code "215") (name "unconnected-(U5-Pad54)") (class "Default")
      (node (ref "U5") (pin "54") (pintype "passive"))
    )
    (net (code "216") (name "unconnected-(U5-RDX_AUX-Pad24)") (class "Default")
      (node (ref "U5") (pin "24") (pinfunction "RDX_AUX_24") (pintype "passive"))
    )
    (net (code "217") (name "unconnected-(U5-RTS-Pad39)") (class "Default")
      (node (ref "U5") (pin "39") (pinfunction "RTS_39") (pintype "passive"))
    )
    (net (code "218") (name "unconnected-(U5-TXD_AUX-Pad25)") (class "Default")
      (node (ref "U5") (pin "25") (pinfunction "TXD_AUX_25") (pintype "passive"))
    )
    (net (code "219") (name "unconnected-(U5-USB_3V3-Pad1)") (class "Default")
      (node (ref "U5") (pin "1") (pinfunction "USB_3V3_1") (pintype "passive"))
    )
    (net (code "220") (name "unconnected-(U5-USB_DM-Pad11)") (class "Default")
      (node (ref "U5") (pin "11") (pinfunction "USB_DM_11") (pintype "passive"))
    )
    (net (code "221") (name "unconnected-(U5-USB_DP-Pad12)") (class "Default")
      (node (ref "U5") (pin "12") (pinfunction "USB_DP_12") (pintype "passive"))
    )
    (net (code "222") (name "unconnected-(U5-USB_MODE-Pad2)") (class "Default")
      (node (ref "U5") (pin "2") (pinfunction "USB_MODE_2") (pintype "passive"))
    )
    (net (code "223") (name "unconnected-(U6-NC-Pad6)") (class "Default")
      (node (ref "U6") (pin "6") (pinfunction "NC_6") (pintype "passive"))
    )
    (net (code "224") (name "unconnected-(U6-NC-Pad9)") (class "Default")
      (node (ref "U6") (pin "9") (pinfunction "NC_9") (pintype "passive"))
    )
    (net (code "225") (name "unconnected-(U8-TNOW-Pad6)") (class "Default")
      (node (ref "U8") (pin "6") (pinfunction "TNOW_6") (pintype "passive"))
    )
    (net (code "226") (name "unconnected-(U8-~{CTS}-Pad5)") (class "Default")
      (node (ref "U8") (pin "5") (pinfunction "~{CTS}_5") (pintype "passive"))
    )
    (net (code "227") (name "unconnected-(U8-~{RTS}-Pad4)") (class "Default")
      (node (ref "U8") (pin "4") (pinfunction "~{RTS}_4") (pintype "passive"))
    )
    (net (code "228") (name "unconnected-(U10-FB-Pad4)") (class "Default")
      (node (ref "U10") (pin "4") (pinfunction "FB_4") (pintype "passive"))
    )
    (net (code "229") (name "unconnected-(U10-PG-Pad6)") (class "Default")
      (node (ref "U10") (pin "6") (pinfunction "PG_6") (pintype "passive"))
    )
  )
)
